# SchedaRobotica.net
KiCad netlist of a schematic drawn in EAGLE
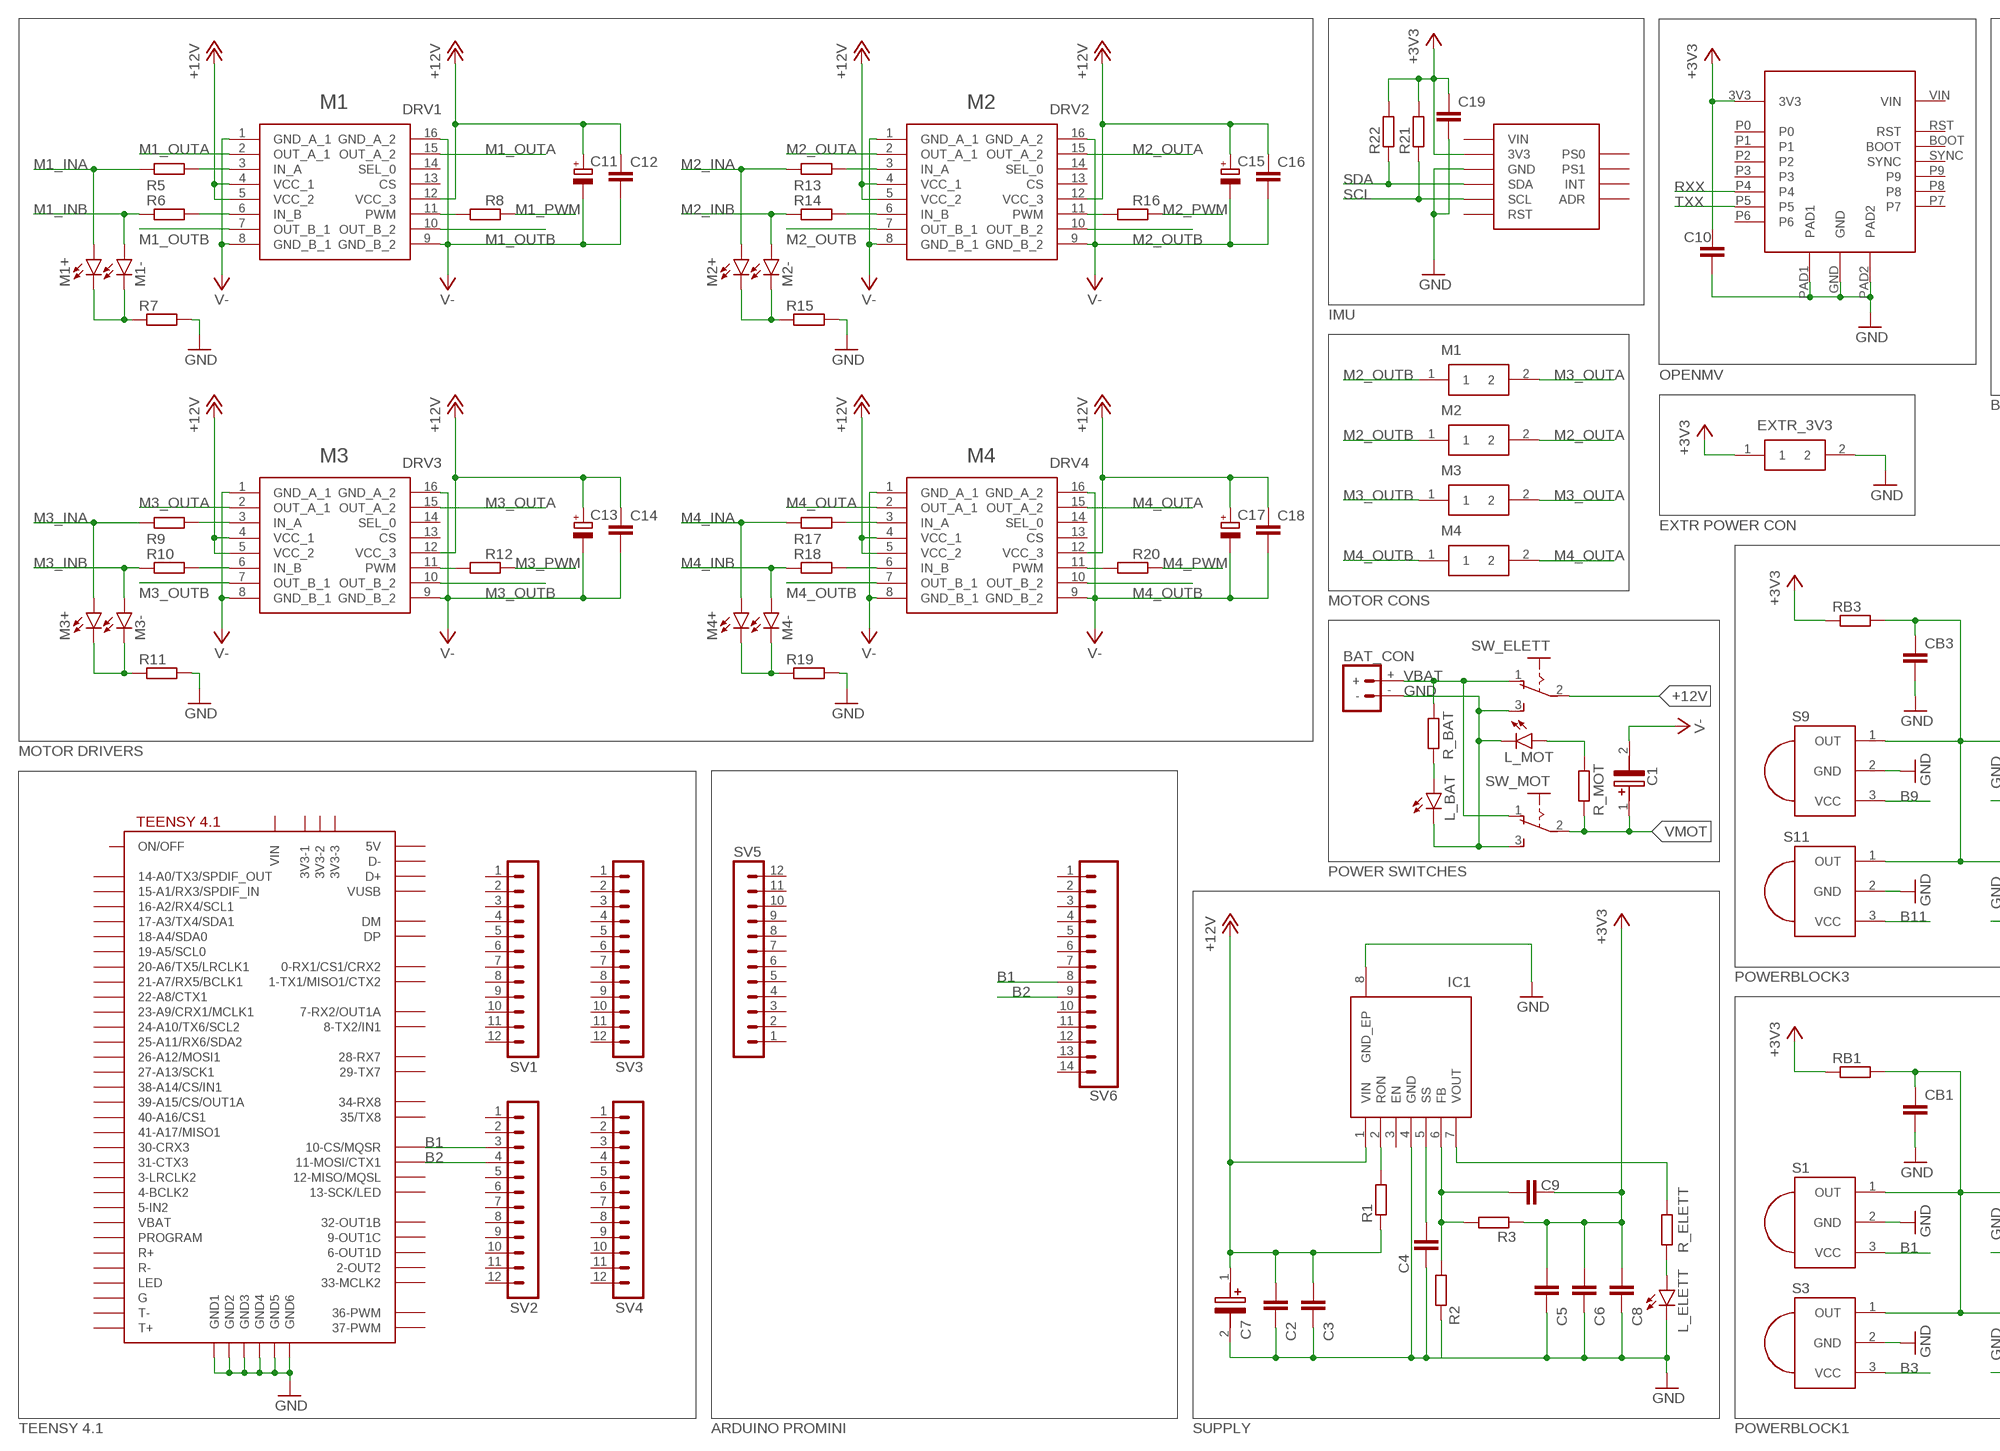
[diagram p0: schematic, sheet 1, part 1 of 2]
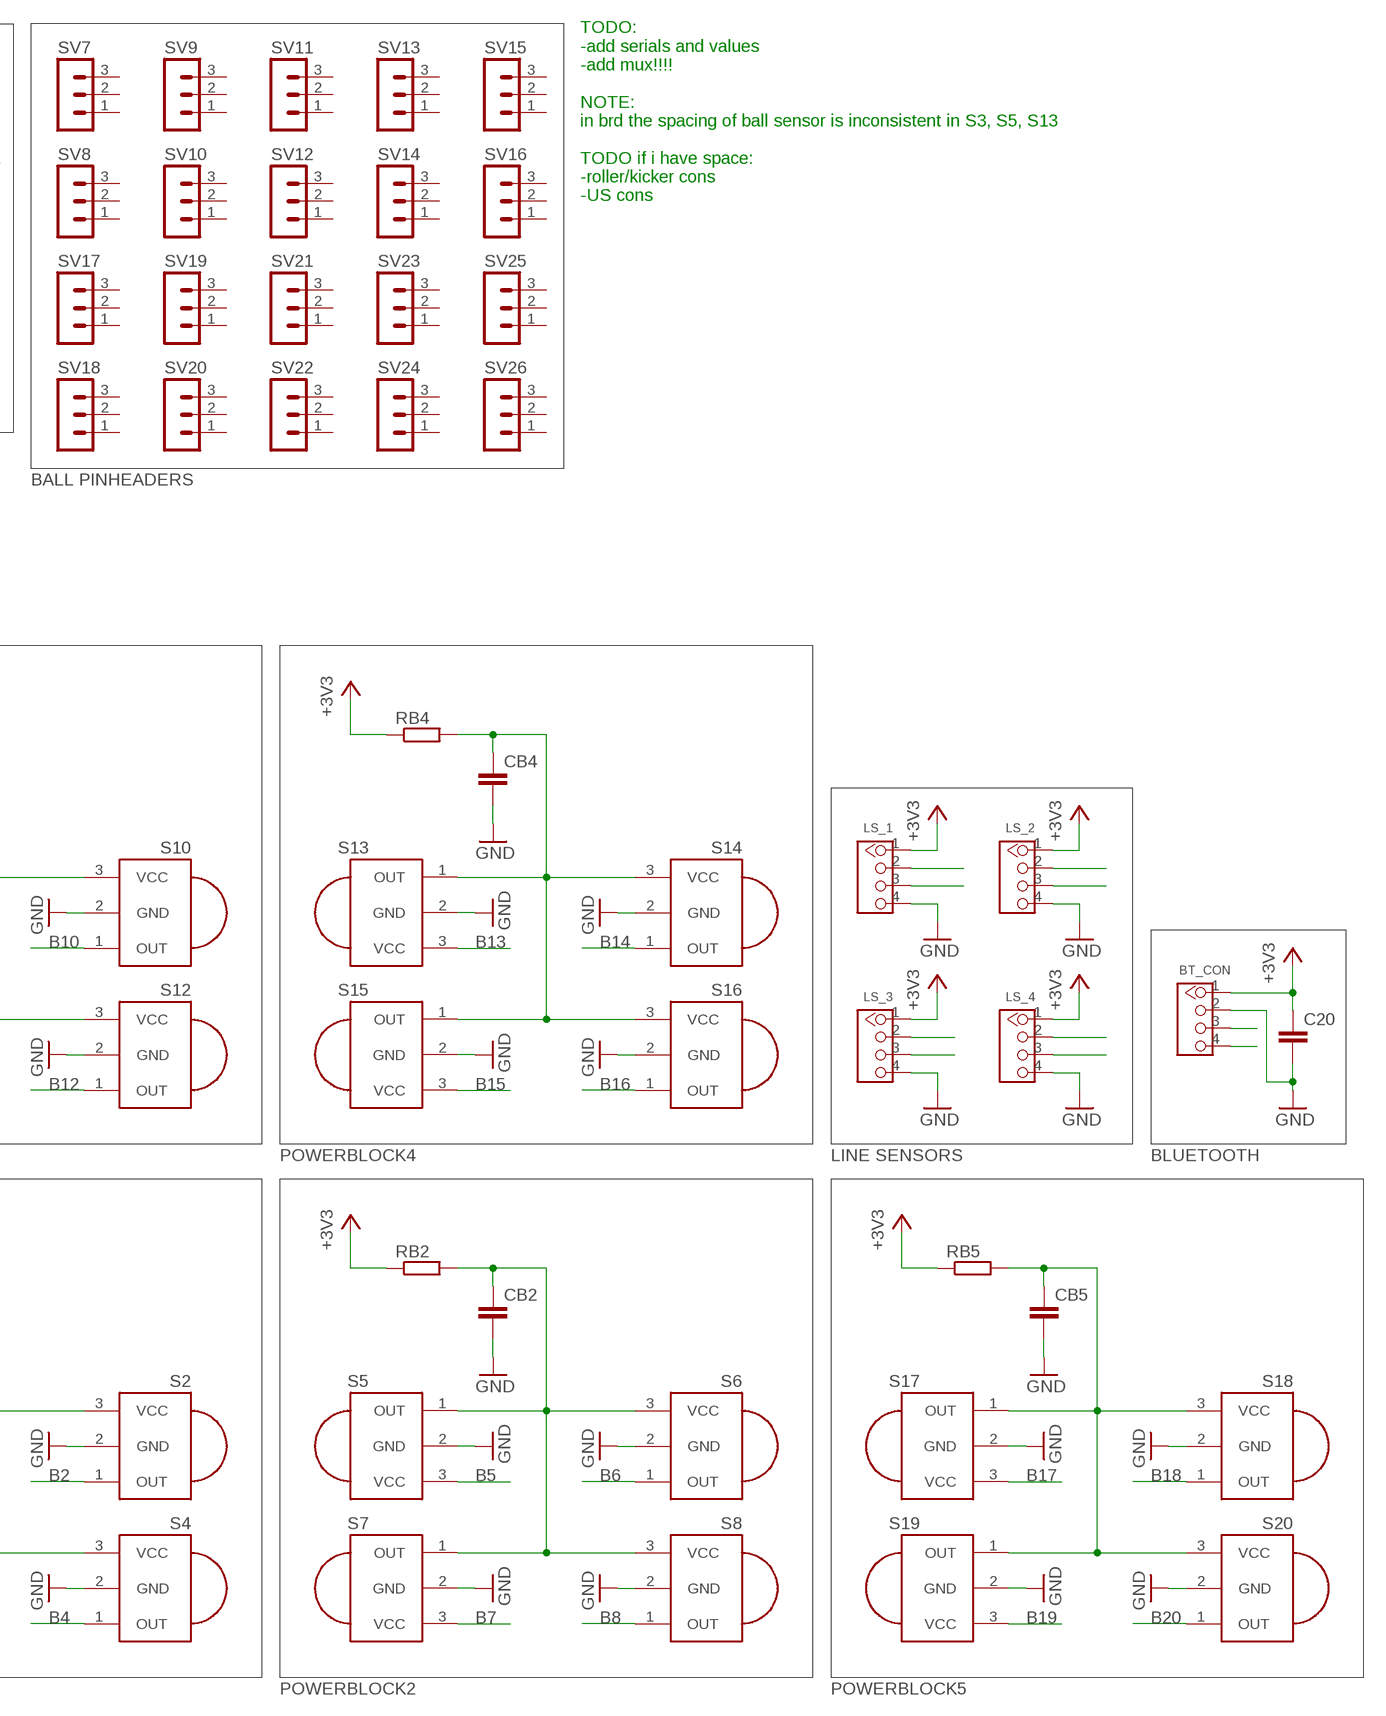
[diagram p1: schematic, sheet 1, part 2 of 2]

(export (version "E")
  (design (tool "Eeschema 10.0.6"))
  (components
    (comp (ref "BAT_CON")
      (value "BATTERY_CONN_DEANS")
      (footprint "eagle-import:DEANS")
      (libsource (lib "eagle-import") (part "BATTERY_CONN_DEANS"))
    )
    (comp (ref "BT_CON")
      (value "4P-2.0")
      (footprint "eagle-import:HW4-2.0")
      (libsource (lib "eagle-import") (part "GROVE-CONNECTOR-DIP(4P-2.0)"))
    )
    (comp (ref "C1")
      (value "EEV-FK1C152Q")
      (footprint "eagle-import:FKV(H13)")
      (fields (field (name "MOUSER_PART_NUMBER") "667-EEV-FK1C152Q"))
      (libsource (lib "eagle-import") (part "EEV-FK1C152Q"))
    )
    (comp (ref "C2")
      (value "100n")
      (footprint "eagle-import:C0805")
      (libsource (lib "eagle-import") (part "C-EUC0805"))
    )
    (comp (ref "C3")
      (value "100n")
      (footprint "eagle-import:C0805")
      (libsource (lib "eagle-import") (part "C-EUC0805"))
    )
    (comp (ref "C4")
      (value "22n")
      (footprint "eagle-import:C0805")
      (libsource (lib "eagle-import") (part "C-EUC0805"))
    )
    (comp (ref "C5")
      (value "100u")
      (footprint "eagle-import:C1206")
      (libsource (lib "eagle-import") (part "C-EUC1206"))
    )
    (comp (ref "C6")
      (value "100u")
      (footprint "eagle-import:C1206")
      (libsource (lib "eagle-import") (part "C-EUC1206"))
    )
    (comp (ref "C7")
      (value "EEV-FK1C152Q")
      (footprint "eagle-import:FKV(H13)")
      (fields (field (name "MOUSER_PART_NUMBER") "667-EEV-FK1C152Q"))
      (libsource (lib "eagle-import") (part "EEV-FK1C152Q"))
    )
    (comp (ref "C8")
      (value "100n")
      (footprint "eagle-import:C0805")
      (libsource (lib "eagle-import") (part "C-EUC0805"))
    )
    (comp (ref "C9")
      (value "22n")
      (footprint "eagle-import:C0805")
      (libsource (lib "eagle-import") (part "C-EUC0805"))
    )
    (comp (ref "C10")
      (value "100u")
      (footprint "eagle-import:C1206")
      (libsource (lib "eagle-import") (part "C-EUC1206"))
    )
    (comp (ref "C11")
      (value "CPOL-EUE")
      (footprint "eagle-import:PANASONIC_E")
      (libsource (lib "eagle-import") (part "CPOL-EUE"))
    )
    (comp (ref "C12")
      (value "C-EUC0805")
      (footprint "eagle-import:C0805")
      (libsource (lib "eagle-import") (part "C-EUC0805"))
    )
    (comp (ref "C13")
      (value "CPOL-EUE")
      (footprint "eagle-import:PANASONIC_E")
      (libsource (lib "eagle-import") (part "CPOL-EUE"))
    )
    (comp (ref "C14")
      (value "C-EUC0805")
      (footprint "eagle-import:C0805")
      (libsource (lib "eagle-import") (part "C-EUC0805"))
    )
    (comp (ref "C15")
      (value "CPOL-EUE")
      (footprint "eagle-import:PANASONIC_E")
      (libsource (lib "eagle-import") (part "CPOL-EUE"))
    )
    (comp (ref "C16")
      (value "C-EUC0805")
      (footprint "eagle-import:C0805")
      (libsource (lib "eagle-import") (part "C-EUC0805"))
    )
    (comp (ref "C17")
      (value "CPOL-EUE")
      (footprint "eagle-import:PANASONIC_E")
      (libsource (lib "eagle-import") (part "CPOL-EUE"))
    )
    (comp (ref "C18")
      (value "C-EUC0805")
      (footprint "eagle-import:C0805")
      (libsource (lib "eagle-import") (part "C-EUC0805"))
    )
    (comp (ref "C19")
      (value "1u")
      (footprint "eagle-import:C0805")
      (libsource (lib "eagle-import") (part "C-EUC0805"))
    )
    (comp (ref "C20")
      (value "1u")
      (footprint "eagle-import:C0805")
      (libsource (lib "eagle-import") (part "C-EUC0805"))
    )
    (comp (ref "CB1")
      (value "C-EUC0805")
      (footprint "eagle-import:C0805")
      (libsource (lib "eagle-import") (part "C-EUC0805"))
    )
    (comp (ref "CB2")
      (value "C-EUC0805")
      (footprint "eagle-import:C0805")
      (libsource (lib "eagle-import") (part "C-EUC0805"))
    )
    (comp (ref "CB3")
      (value "C-EUC0805")
      (footprint "eagle-import:C0805")
      (libsource (lib "eagle-import") (part "C-EUC0805"))
    )
    (comp (ref "CB4")
      (value "C-EUC0805")
      (footprint "eagle-import:C0805")
      (libsource (lib "eagle-import") (part "C-EUC0805"))
    )
    (comp (ref "CB5")
      (value "C-EUC0805")
      (footprint "eagle-import:C0805")
      (libsource (lib "eagle-import") (part "C-EUC0805"))
    )
    (comp (ref "DRV1")
      (value "VNH7070ASTR")
      (footprint "eagle-import:SOIC127P600X175-16N")
      (fields
        (field (name "MOUSER_PART_NUMBER") "511-VNH7070ASTR")
        (field (name "RS_PART_NUMBER") "1647017P")
      )
      (libsource (lib "eagle-import") (part "VNH7070ASTR"))
    )
    (comp (ref "DRV2")
      (value "VNH7070ASTR")
      (footprint "eagle-import:SOIC127P600X175-16N")
      (fields
        (field (name "MOUSER_PART_NUMBER") "511-VNH7070ASTR")
        (field (name "RS_PART_NUMBER") "1647017P")
      )
      (libsource (lib "eagle-import") (part "VNH7070ASTR"))
    )
    (comp (ref "DRV3")
      (value "VNH7070ASTR")
      (footprint "eagle-import:SOIC127P600X175-16N")
      (fields
        (field (name "MOUSER_PART_NUMBER") "511-VNH7070ASTR")
        (field (name "RS_PART_NUMBER") "1647017P")
      )
      (libsource (lib "eagle-import") (part "VNH7070ASTR"))
    )
    (comp (ref "DRV4")
      (value "VNH7070ASTR")
      (footprint "eagle-import:SOIC127P600X175-16N")
      (fields
        (field (name "MOUSER_PART_NUMBER") "511-VNH7070ASTR")
        (field (name "RS_PART_NUMBER") "1647017P")
      )
      (libsource (lib "eagle-import") (part "VNH7070ASTR"))
    )
    (comp (ref "EXTR_3V3")
      (value "43650-0201")
      (footprint "eagle-import:43650-0200")
      (fields (field (name "MOUSER_PART_NUMBER") "538-43650-0201"))
      (libsource (lib "eagle-import") (part "43650-0201"))
    )
    (comp (ref "IC1")
      (value "LMZ14202TZE-ADJ_NOPB")
      (footprint "eagle-import:NDW0007A")
      (fields
        (field (name "MANUFACTURER_PART_NUMBER") "LMZ14202TZE-ADJ/NOPB")
        (field (name "MOUSER_PART_NUMBER") "926-LM14202TZEADJNPB")
        (field (name "RS_PART_NUMBER") "7981195P")
      )
      (libsource (lib "eagle-import") (part "LMZ14202TZE-ADJ_NOPB"))
    )
    (comp (ref "LS_1")
      (value "4P-2.0")
      (footprint "eagle-import:HW4-2.0")
      (libsource (lib "eagle-import") (part "GROVE-CONNECTOR-DIP(4P-2.0)"))
    )
    (comp (ref "LS_2")
      (value "4P-2.0")
      (footprint "eagle-import:HW4-2.0")
      (libsource (lib "eagle-import") (part "GROVE-CONNECTOR-DIP(4P-2.0)"))
    )
    (comp (ref "LS_3")
      (value "4P-2.0")
      (footprint "eagle-import:HW4-2.0")
      (libsource (lib "eagle-import") (part "GROVE-CONNECTOR-DIP(4P-2.0)"))
    )
    (comp (ref "LS_4")
      (value "4P-2.0")
      (footprint "eagle-import:HW4-2.0")
      (libsource (lib "eagle-import") (part "GROVE-CONNECTOR-DIP(4P-2.0)"))
    )
    (comp (ref "L_BAT")
      (value "LEDCHIPLED_1206")
      (footprint "eagle-import:CHIPLED_1206")
      (libsource (lib "eagle-import") (part "LEDCHIPLED_1206"))
    )
    (comp (ref "L_ELETT")
      (value "LEDCHIPLED_1206")
      (footprint "eagle-import:CHIPLED_1206")
      (libsource (lib "eagle-import") (part "LEDCHIPLED_1206"))
    )
    (comp (ref "L_MOT")
      (value "LEDCHIPLED_1206")
      (footprint "eagle-import:CHIPLED_1206")
      (libsource (lib "eagle-import") (part "LEDCHIPLED_1206"))
    )
    (comp (ref "M1")
      (value "43650-0201")
      (footprint "eagle-import:43650-0200")
      (fields (field (name "MOUSER_PART_NUMBER") "538-43650-0201"))
      (libsource (lib "eagle-import") (part "43650-0201"))
    )
    (comp (ref "M1+")
      (value "LEDCHIPLED_1206")
      (footprint "eagle-import:CHIPLED_1206")
      (libsource (lib "eagle-import") (part "LEDCHIPLED_1206"))
    )
    (comp (ref "M1-")
      (value "LEDCHIPLED_1206")
      (footprint "eagle-import:CHIPLED_1206")
      (libsource (lib "eagle-import") (part "LEDCHIPLED_1206"))
    )
    (comp (ref "M2")
      (value "43650-0201")
      (footprint "eagle-import:43650-0200")
      (fields (field (name "MOUSER_PART_NUMBER") "538-43650-0201"))
      (libsource (lib "eagle-import") (part "43650-0201"))
    )
    (comp (ref "M2+")
      (value "LEDCHIPLED_1206")
      (footprint "eagle-import:CHIPLED_1206")
      (libsource (lib "eagle-import") (part "LEDCHIPLED_1206"))
    )
    (comp (ref "M2-")
      (value "LEDCHIPLED_1206")
      (footprint "eagle-import:CHIPLED_1206")
      (libsource (lib "eagle-import") (part "LEDCHIPLED_1206"))
    )
    (comp (ref "M3")
      (value "43650-0201")
      (footprint "eagle-import:43650-0200")
      (fields (field (name "MOUSER_PART_NUMBER") "538-43650-0201"))
      (libsource (lib "eagle-import") (part "43650-0201"))
    )
    (comp (ref "M3+")
      (value "LEDCHIPLED_1206")
      (footprint "eagle-import:CHIPLED_1206")
      (libsource (lib "eagle-import") (part "LEDCHIPLED_1206"))
    )
    (comp (ref "M3-")
      (value "LEDCHIPLED_1206")
      (footprint "eagle-import:CHIPLED_1206")
      (libsource (lib "eagle-import") (part "LEDCHIPLED_1206"))
    )
    (comp (ref "M4")
      (value "43650-0201")
      (footprint "eagle-import:43650-0200")
      (fields (field (name "MOUSER_PART_NUMBER") "538-43650-0201"))
      (libsource (lib "eagle-import") (part "43650-0201"))
    )
    (comp (ref "M4+")
      (value "LEDCHIPLED_1206")
      (footprint "eagle-import:CHIPLED_1206")
      (libsource (lib "eagle-import") (part "LEDCHIPLED_1206"))
    )
    (comp (ref "M4-")
      (value "LEDCHIPLED_1206")
      (footprint "eagle-import:CHIPLED_1206")
      (libsource (lib "eagle-import") (part "LEDCHIPLED_1206"))
    )
    (comp (ref "R1")
      (value "61,9k")
      (footprint "eagle-import:M0805")
      (libsource (lib "eagle-import") (part "R-EU_M0805"))
    )
    (comp (ref "R2")
      (value "1,07k")
      (footprint "eagle-import:M0805")
      (libsource (lib "eagle-import") (part "R-EU_M0805"))
    )
    (comp (ref "R3")
      (value "3,32k")
      (footprint "eagle-import:M0805")
      (libsource (lib "eagle-import") (part "R-EU_M0805"))
    )
    (comp (ref "R5")
      (value "R-EU_M0805")
      (footprint "eagle-import:M0805")
      (libsource (lib "eagle-import") (part "R-EU_M0805"))
    )
    (comp (ref "R6")
      (value "R-EU_M0805")
      (footprint "eagle-import:M0805")
      (libsource (lib "eagle-import") (part "R-EU_M0805"))
    )
    (comp (ref "R7")
      (value "R-EU_M0805")
      (footprint "eagle-import:M0805")
      (libsource (lib "eagle-import") (part "R-EU_M0805"))
    )
    (comp (ref "R8")
      (value "R-EU_M0805")
      (footprint "eagle-import:M0805")
      (libsource (lib "eagle-import") (part "R-EU_M0805"))
    )
    (comp (ref "R9")
      (value "R-EU_M0805")
      (footprint "eagle-import:M0805")
      (libsource (lib "eagle-import") (part "R-EU_M0805"))
    )
    (comp (ref "R10")
      (value "R-EU_M0805")
      (footprint "eagle-import:M0805")
      (libsource (lib "eagle-import") (part "R-EU_M0805"))
    )
    (comp (ref "R11")
      (value "R-EU_M0805")
      (footprint "eagle-import:M0805")
      (libsource (lib "eagle-import") (part "R-EU_M0805"))
    )
    (comp (ref "R12")
      (value "R-EU_M0805")
      (footprint "eagle-import:M0805")
      (libsource (lib "eagle-import") (part "R-EU_M0805"))
    )
    (comp (ref "R13")
      (value "R-EU_M0805")
      (footprint "eagle-import:M0805")
      (libsource (lib "eagle-import") (part "R-EU_M0805"))
    )
    (comp (ref "R14")
      (value "R-EU_M0805")
      (footprint "eagle-import:M0805")
      (libsource (lib "eagle-import") (part "R-EU_M0805"))
    )
    (comp (ref "R15")
      (value "R-EU_M0805")
      (footprint "eagle-import:M0805")
      (libsource (lib "eagle-import") (part "R-EU_M0805"))
    )
    (comp (ref "R16")
      (value "R-EU_M0805")
      (footprint "eagle-import:M0805")
      (libsource (lib "eagle-import") (part "R-EU_M0805"))
    )
    (comp (ref "R17")
      (value "R-EU_M0805")
      (footprint "eagle-import:M0805")
      (libsource (lib "eagle-import") (part "R-EU_M0805"))
    )
    (comp (ref "R18")
      (value "R-EU_M0805")
      (footprint "eagle-import:M0805")
      (libsource (lib "eagle-import") (part "R-EU_M0805"))
    )
    (comp (ref "R19")
      (value "R-EU_M0805")
      (footprint "eagle-import:M0805")
      (libsource (lib "eagle-import") (part "R-EU_M0805"))
    )
    (comp (ref "R20")
      (value "R-EU_M0805")
      (footprint "eagle-import:M0805")
      (libsource (lib "eagle-import") (part "R-EU_M0805"))
    )
    (comp (ref "R21")
      (value "10k")
      (footprint "eagle-import:M0805")
      (libsource (lib "eagle-import") (part "R-EU_M0805"))
    )
    (comp (ref "R22")
      (value "10k")
      (footprint "eagle-import:M0805")
      (libsource (lib "eagle-import") (part "R-EU_M0805"))
    )
    (comp (ref "RB1")
      (value "R-EU_M0805")
      (footprint "eagle-import:M0805")
      (libsource (lib "eagle-import") (part "R-EU_M0805"))
    )
    (comp (ref "RB2")
      (value "R-EU_M0805")
      (footprint "eagle-import:M0805")
      (libsource (lib "eagle-import") (part "R-EU_M0805"))
    )
    (comp (ref "RB3")
      (value "R-EU_M0805")
      (footprint "eagle-import:M0805")
      (libsource (lib "eagle-import") (part "R-EU_M0805"))
    )
    (comp (ref "RB4")
      (value "R-EU_M0805")
      (footprint "eagle-import:M0805")
      (libsource (lib "eagle-import") (part "R-EU_M0805"))
    )
    (comp (ref "RB5")
      (value "R-EU_M0805")
      (footprint "eagle-import:M0805")
      (libsource (lib "eagle-import") (part "R-EU_M0805"))
    )
    (comp (ref "R_BAT")
      (value "R-EU_M0805")
      (footprint "eagle-import:M0805")
      (libsource (lib "eagle-import") (part "R-EU_M0805"))
    )
    (comp (ref "R_ELETT")
      (value "R-EU_M0805")
      (footprint "eagle-import:M0805")
      (libsource (lib "eagle-import") (part "R-EU_M0805"))
    )
    (comp (ref "R_MOT")
      (value "R-EU_M0805")
      (footprint "eagle-import:M0805")
      (libsource (lib "eagle-import") (part "R-EU_M0805"))
    )
    (comp (ref "S1")
      (value "PNA460XM")
      (footprint "eagle-import:PNA460XM")
      (libsource (lib "eagle-import") (part "PNA460XM"))
    )
    (comp (ref "S2")
      (value "PNA460XM")
      (footprint "eagle-import:PNA460XM")
      (libsource (lib "eagle-import") (part "PNA460XM"))
    )
    (comp (ref "S3")
      (value "PNA460XM")
      (footprint "eagle-import:PNA460XM")
      (libsource (lib "eagle-import") (part "PNA460XM"))
    )
    (comp (ref "S4")
      (value "PNA460XM")
      (footprint "eagle-import:PNA460XM")
      (libsource (lib "eagle-import") (part "PNA460XM"))
    )
    (comp (ref "S5")
      (value "PNA460XM")
      (footprint "eagle-import:PNA460XM")
      (libsource (lib "eagle-import") (part "PNA460XM"))
    )
    (comp (ref "S6")
      (value "PNA460XM")
      (footprint "eagle-import:PNA460XM")
      (libsource (lib "eagle-import") (part "PNA460XM"))
    )
    (comp (ref "S7")
      (value "PNA460XM")
      (footprint "eagle-import:PNA460XM")
      (libsource (lib "eagle-import") (part "PNA460XM"))
    )
    (comp (ref "S8")
      (value "PNA460XM")
      (footprint "eagle-import:PNA460XM")
      (libsource (lib "eagle-import") (part "PNA460XM"))
    )
    (comp (ref "S9")
      (value "PNA460XM")
      (footprint "eagle-import:PNA460XM")
      (libsource (lib "eagle-import") (part "PNA460XM"))
    )
    (comp (ref "S10")
      (value "PNA460XM")
      (footprint "eagle-import:PNA460XM")
      (libsource (lib "eagle-import") (part "PNA460XM"))
    )
    (comp (ref "S11")
      (value "PNA460XM")
      (footprint "eagle-import:PNA460XM")
      (libsource (lib "eagle-import") (part "PNA460XM"))
    )
    (comp (ref "S12")
      (value "PNA460XM")
      (footprint "eagle-import:PNA460XM")
      (libsource (lib "eagle-import") (part "PNA460XM"))
    )
    (comp (ref "S13")
      (value "PNA460XM")
      (footprint "eagle-import:PNA460XM")
      (libsource (lib "eagle-import") (part "PNA460XM"))
    )
    (comp (ref "S14")
      (value "PNA460XM")
      (footprint "eagle-import:PNA460XM")
      (libsource (lib "eagle-import") (part "PNA460XM"))
    )
    (comp (ref "S15")
      (value "PNA460XM")
      (footprint "eagle-import:PNA460XM")
      (libsource (lib "eagle-import") (part "PNA460XM"))
    )
    (comp (ref "S16")
      (value "PNA460XM")
      (footprint "eagle-import:PNA460XM")
      (libsource (lib "eagle-import") (part "PNA460XM"))
    )
    (comp (ref "S17")
      (value "PNA460XM")
      (footprint "eagle-import:PNA460XM")
      (libsource (lib "eagle-import") (part "PNA460XM"))
    )
    (comp (ref "S18")
      (value "PNA460XM")
      (footprint "eagle-import:PNA460XM")
      (libsource (lib "eagle-import") (part "PNA460XM"))
    )
    (comp (ref "S19")
      (value "PNA460XM")
      (footprint "eagle-import:PNA460XM")
      (libsource (lib "eagle-import") (part "PNA460XM"))
    )
    (comp (ref "S20")
      (value "PNA460XM")
      (footprint "eagle-import:PNA460XM")
      (libsource (lib "eagle-import") (part "PNA460XM"))
    )
    (comp (ref "SV1")
      (value "MA12-1")
      (footprint "eagle-import:MA12-1")
      (libsource (lib "eagle-import") (part "MA12-1"))
    )
    (comp (ref "SV2")
      (value "MA12-1")
      (footprint "eagle-import:MA12-1")
      (libsource (lib "eagle-import") (part "MA12-1"))
    )
    (comp (ref "SV3")
      (value "MA12-1")
      (footprint "eagle-import:MA12-1")
      (libsource (lib "eagle-import") (part "MA12-1"))
    )
    (comp (ref "SV4")
      (value "MA12-1")
      (footprint "eagle-import:MA12-1")
      (libsource (lib "eagle-import") (part "MA12-1"))
    )
    (comp (ref "SV5")
      (value "MA12-1")
      (footprint "eagle-import:MA12-1")
      (libsource (lib "eagle-import") (part "MA12-1"))
    )
    (comp (ref "SV6")
      (value "CONN_14LONGPADS")
      (footprint "eagle-import:1X14-LONGPADS")
      (libsource (lib "eagle-import") (part "CONN_14LONGPADS"))
    )
    (comp (ref "SV7")
      (value "MA03-1")
      (footprint "eagle-import:MA03-1")
      (libsource (lib "eagle-import") (part "MA03-1"))
    )
    (comp (ref "SV8")
      (value "MA03-1")
      (footprint "eagle-import:MA03-1")
      (libsource (lib "eagle-import") (part "MA03-1"))
    )
    (comp (ref "SV9")
      (value "MA03-1")
      (footprint "eagle-import:MA03-1")
      (libsource (lib "eagle-import") (part "MA03-1"))
    )
    (comp (ref "SV10")
      (value "MA03-1")
      (footprint "eagle-import:MA03-1")
      (libsource (lib "eagle-import") (part "MA03-1"))
    )
    (comp (ref "SV11")
      (value "MA03-1")
      (footprint "eagle-import:MA03-1")
      (libsource (lib "eagle-import") (part "MA03-1"))
    )
    (comp (ref "SV12")
      (value "MA03-1")
      (footprint "eagle-import:MA03-1")
      (libsource (lib "eagle-import") (part "MA03-1"))
    )
    (comp (ref "SV13")
      (value "MA03-1")
      (footprint "eagle-import:MA03-1")
      (libsource (lib "eagle-import") (part "MA03-1"))
    )
    (comp (ref "SV14")
      (value "MA03-1")
      (footprint "eagle-import:MA03-1")
      (libsource (lib "eagle-import") (part "MA03-1"))
    )
    (comp (ref "SV15")
      (value "MA03-1")
      (footprint "eagle-import:MA03-1")
      (libsource (lib "eagle-import") (part "MA03-1"))
    )
    (comp (ref "SV16")
      (value "MA03-1")
      (footprint "eagle-import:MA03-1")
      (libsource (lib "eagle-import") (part "MA03-1"))
    )
    (comp (ref "SV17")
      (value "MA03-1")
      (footprint "eagle-import:MA03-1")
      (libsource (lib "eagle-import") (part "MA03-1"))
    )
    (comp (ref "SV18")
      (value "MA03-1")
      (footprint "eagle-import:MA03-1")
      (libsource (lib "eagle-import") (part "MA03-1"))
    )
    (comp (ref "SV19")
      (value "MA03-1")
      (footprint "eagle-import:MA03-1")
      (libsource (lib "eagle-import") (part "MA03-1"))
    )
    (comp (ref "SV20")
      (value "MA03-1")
      (footprint "eagle-import:MA03-1")
      (libsource (lib "eagle-import") (part "MA03-1"))
    )
    (comp (ref "SV21")
      (value "MA03-1")
      (footprint "eagle-import:MA03-1")
      (libsource (lib "eagle-import") (part "MA03-1"))
    )
    (comp (ref "SV22")
      (value "MA03-1")
      (footprint "eagle-import:MA03-1")
      (libsource (lib "eagle-import") (part "MA03-1"))
    )
    (comp (ref "SV23")
      (value "MA03-1")
      (footprint "eagle-import:MA03-1")
      (libsource (lib "eagle-import") (part "MA03-1"))
    )
    (comp (ref "SV24")
      (value "MA03-1")
      (footprint "eagle-import:MA03-1")
      (libsource (lib "eagle-import") (part "MA03-1"))
    )
    (comp (ref "SV25")
      (value "MA03-1")
      (footprint "eagle-import:MA03-1")
      (libsource (lib "eagle-import") (part "MA03-1"))
    )
    (comp (ref "SV26")
      (value "MA03-1")
      (footprint "eagle-import:MA03-1")
      (libsource (lib "eagle-import") (part "MA03-1"))
    )
    (comp (ref "SW_ELETT")
      (value "255SB")
      (footprint "eagle-import:255SB")
      (libsource (lib "eagle-import") (part "255SB"))
    )
    (comp (ref "SW_MOT")
      (value "255SB")
      (footprint "eagle-import:255SB")
      (libsource (lib "eagle-import") (part "255SB"))
    )
    (comp (ref "U$1")
      (value "TEENSY41")
      (footprint "eagle-import:TEENSY41")
      (libsource (lib "eagle-import") (part "TEENSY41"))
    )
    (comp (ref "U$2")
      (value "OPENMV_H7")
      (footprint "eagle-import:OPENMV_H7")
      (libsource (lib "eagle-import") (part "OPENMV_H7"))
    )
    (comp (ref "U$3")
      (value "BNO055_BNO055")
      (footprint "eagle-import:BNO055_BNO055")
      (libsource (lib "eagle-import") (part "BNO055_BNO055"))
    )
  )
  (nets
    (net (code "1") (name "+3V3") (class "Default")
      (node (ref "BT_CON") (pin "1") (pinfunction "1_1") (pintype "bidirectional"))
      (node (ref "C10") (pin "1") (pinfunction "1_1") (pintype "passive"))
      (node (ref "C19") (pin "1") (pinfunction "1_1") (pintype "passive"))
      (node (ref "C20") (pin "1") (pinfunction "1_1") (pintype "passive"))
      (node (ref "C5") (pin "1") (pinfunction "1_1") (pintype "passive"))
      (node (ref "C6") (pin "1") (pinfunction "1_1") (pintype "passive"))
      (node (ref "C8") (pin "1") (pinfunction "1_1") (pintype "passive"))
      (node (ref "C9") (pin "2") (pinfunction "2_2") (pintype "passive"))
      (node (ref "EXTR_3V3") (pin "1") (pinfunction "1_1") (pintype "bidirectional"))
      (node (ref "LS_1") (pin "1") (pinfunction "1_1") (pintype "bidirectional"))
      (node (ref "LS_2") (pin "1") (pinfunction "1_1") (pintype "bidirectional"))
      (node (ref "LS_3") (pin "1") (pinfunction "1_1") (pintype "bidirectional"))
      (node (ref "LS_4") (pin "1") (pinfunction "1_1") (pintype "bidirectional"))
      (node (ref "R21") (pin "2") (pinfunction "2_2") (pintype "passive"))
      (node (ref "R22") (pin "2") (pinfunction "2_2") (pintype "passive"))
      (node (ref "R3") (pin "1") (pinfunction "1_1") (pintype "passive"))
      (node (ref "RB1") (pin "1") (pinfunction "1_1") (pintype "passive"))
      (node (ref "RB2") (pin "1") (pinfunction "1_1") (pintype "passive"))
      (node (ref "RB3") (pin "1") (pinfunction "1_1") (pintype "passive"))
      (node (ref "RB4") (pin "1") (pinfunction "1_1") (pintype "passive"))
      (node (ref "RB5") (pin "1") (pinfunction "1_1") (pintype "passive"))
      (node (ref "U$2") (pin "3V3") (pinfunction "3V3_3V3") (pintype "bidirectional"))
      (node (ref "U$3") (pin "3V3") (pinfunction "3V3_3V3") (pintype "bidirectional"))
    )
    (net (code "2") (name "+12V") (class "Default")
      (node (ref "C11") (pin "+") (pinfunction "+_+") (pintype "passive"))
      (node (ref "C12") (pin "1") (pinfunction "1_1") (pintype "passive"))
      (node (ref "C13") (pin "+") (pinfunction "+_+") (pintype "passive"))
      (node (ref "C14") (pin "1") (pinfunction "1_1") (pintype "passive"))
      (node (ref "C15") (pin "+") (pinfunction "+_+") (pintype "passive"))
      (node (ref "C16") (pin "1") (pinfunction "1_1") (pintype "passive"))
      (node (ref "C17") (pin "+") (pinfunction "+_+") (pintype "passive"))
      (node (ref "C18") (pin "1") (pinfunction "1_1") (pintype "passive"))
      (node (ref "C2") (pin "1") (pinfunction "1_1") (pintype "passive"))
      (node (ref "C3") (pin "1") (pinfunction "1_1") (pintype "passive"))
      (node (ref "C7") (pin "1") (pinfunction "+_1") (pintype "bidirectional"))
      (node (ref "DRV1") (pin "12") (pinfunction "VCC_3_12") (pintype "bidirectional"))
      (node (ref "DRV1") (pin "4") (pinfunction "VCC_1_4") (pintype "bidirectional"))
      (node (ref "DRV1") (pin "5") (pinfunction "VCC_2_5") (pintype "bidirectional"))
      (node (ref "DRV2") (pin "12") (pinfunction "VCC_3_12") (pintype "bidirectional"))
      (node (ref "DRV2") (pin "4") (pinfunction "VCC_1_4") (pintype "bidirectional"))
      (node (ref "DRV2") (pin "5") (pinfunction "VCC_2_5") (pintype "bidirectional"))
      (node (ref "DRV3") (pin "12") (pinfunction "VCC_3_12") (pintype "bidirectional"))
      (node (ref "DRV3") (pin "4") (pinfunction "VCC_1_4") (pintype "bidirectional"))
      (node (ref "DRV3") (pin "5") (pinfunction "VCC_2_5") (pintype "bidirectional"))
      (node (ref "DRV4") (pin "12") (pinfunction "VCC_3_12") (pintype "bidirectional"))
      (node (ref "DRV4") (pin "4") (pinfunction "VCC_1_4") (pintype "bidirectional"))
      (node (ref "DRV4") (pin "5") (pinfunction "VCC_2_5") (pintype "bidirectional"))
      (node (ref "IC1") (pin "1") (pinfunction "VIN_1") (pintype "input"))
      (node (ref "R1") (pin "1") (pinfunction "1_1") (pintype "passive"))
      (node (ref "SW_ELETT") (pin "2") (pinfunction "P_2") (pintype "passive"))
    )
    (net (code "3") (name "/B1") (class "Default")
      (node (ref "S1") (pin "3") (pinfunction "VCC_3") (pintype "power_in"))
      (node (ref "SV2") (pin "3") (pinfunction "3_3") (pintype "passive"))
      (node (ref "SV6") (pin "8") (pinfunction "8_8") (pintype "passive"))
      (node (ref "U$1") (pin "10-CS\\MQSR") (pinfunction "10-CS/MQSR_10-CS\\MQSR") (pintype "bidirectional"))
    )
    (net (code "4") (name "/B2") (class "Default")
      (node (ref "S2") (pin "1") (pinfunction "OUT_1") (pintype "output"))
      (node (ref "SV2") (pin "4") (pinfunction "4_4") (pintype "passive"))
      (node (ref "SV6") (pin "9") (pinfunction "9_9") (pintype "passive"))
      (node (ref "U$1") (pin "11-MOSI/CTX1") (pinfunction "11-MOSI/CTX1_11-MOSI/CTX1") (pintype "bidirectional"))
    )
    (net (code "5") (name "/B3") (class "Default")
      (node (ref "S3") (pin "3") (pinfunction "VCC_3") (pintype "power_in"))
    )
    (net (code "6") (name "/B4") (class "Default")
      (node (ref "S4") (pin "1") (pinfunction "OUT_1") (pintype "output"))
    )
    (net (code "7") (name "/B5") (class "Default")
      (node (ref "S5") (pin "3") (pinfunction "VCC_3") (pintype "power_in"))
    )
    (net (code "8") (name "/B6") (class "Default")
      (node (ref "S6") (pin "1") (pinfunction "OUT_1") (pintype "output"))
    )
    (net (code "9") (name "/B7") (class "Default")
      (node (ref "S7") (pin "3") (pinfunction "VCC_3") (pintype "power_in"))
    )
    (net (code "10") (name "/B8") (class "Default")
      (node (ref "S8") (pin "1") (pinfunction "OUT_1") (pintype "output"))
    )
    (net (code "11") (name "/B9") (class "Default")
      (node (ref "S9") (pin "3") (pinfunction "VCC_3") (pintype "power_in"))
    )
    (net (code "12") (name "/B10") (class "Default")
      (node (ref "S10") (pin "1") (pinfunction "OUT_1") (pintype "output"))
    )
    (net (code "13") (name "/B11") (class "Default")
      (node (ref "S11") (pin "3") (pinfunction "VCC_3") (pintype "power_in"))
    )
    (net (code "14") (name "/B12") (class "Default")
      (node (ref "S12") (pin "1") (pinfunction "OUT_1") (pintype "output"))
    )
    (net (code "15") (name "/B13") (class "Default")
      (node (ref "S13") (pin "3") (pinfunction "VCC_3") (pintype "power_in"))
    )
    (net (code "16") (name "/B14") (class "Default")
      (node (ref "S14") (pin "1") (pinfunction "OUT_1") (pintype "output"))
    )
    (net (code "17") (name "/B15") (class "Default")
      (node (ref "S15") (pin "3") (pinfunction "VCC_3") (pintype "power_in"))
    )
    (net (code "18") (name "/B16") (class "Default")
      (node (ref "S16") (pin "1") (pinfunction "OUT_1") (pintype "output"))
    )
    (net (code "19") (name "/B17") (class "Default")
      (node (ref "S17") (pin "3") (pinfunction "VCC_3") (pintype "power_in"))
    )
    (net (code "20") (name "/B18") (class "Default")
      (node (ref "S18") (pin "1") (pinfunction "OUT_1") (pintype "output"))
    )
    (net (code "21") (name "/B19") (class "Default")
      (node (ref "S19") (pin "3") (pinfunction "VCC_3") (pintype "power_in"))
    )
    (net (code "22") (name "/B20") (class "Default")
      (node (ref "S20") (pin "1") (pinfunction "OUT_1") (pintype "output"))
    )
    (net (code "23") (name "/M1_INA") (class "Default")
      (node (ref "M1+") (pin "A") (pinfunction "A_A") (pintype "passive"))
      (node (ref "R5") (pin "1") (pinfunction "1_1") (pintype "passive"))
    )
    (net (code "24") (name "/M1_INB") (class "Default")
      (node (ref "M1-") (pin "A") (pinfunction "A_A") (pintype "passive"))
      (node (ref "R6") (pin "1") (pinfunction "1_1") (pintype "passive"))
    )
    (net (code "25") (name "/M1_OUTA") (class "Default")
      (node (ref "DRV1") (pin "15") (pinfunction "OUT_A_2_15") (pintype "bidirectional"))
      (node (ref "DRV1") (pin "2") (pinfunction "OUT_A_1_2") (pintype "bidirectional"))
    )
    (net (code "26") (name "/M1_OUTB") (class "Default")
      (node (ref "DRV1") (pin "10") (pinfunction "OUT_B_2_10") (pintype "bidirectional"))
      (node (ref "DRV1") (pin "7") (pinfunction "OUT_B_1_7") (pintype "bidirectional"))
    )
    (net (code "27") (name "/M1_PWM") (class "Default")
      (node (ref "R8") (pin "2") (pinfunction "2_2") (pintype "passive"))
    )
    (net (code "28") (name "/M2_INA") (class "Default")
      (node (ref "M2+") (pin "A") (pinfunction "A_A") (pintype "passive"))
      (node (ref "R13") (pin "1") (pinfunction "1_1") (pintype "passive"))
    )
    (net (code "29") (name "/M2_INB") (class "Default")
      (node (ref "M2-") (pin "A") (pinfunction "A_A") (pintype "passive"))
      (node (ref "R14") (pin "1") (pinfunction "1_1") (pintype "passive"))
    )
    (net (code "30") (name "/M2_OUTA") (class "Default")
      (node (ref "DRV2") (pin "15") (pinfunction "OUT_A_2_15") (pintype "bidirectional"))
      (node (ref "DRV2") (pin "2") (pinfunction "OUT_A_1_2") (pintype "bidirectional"))
      (node (ref "M2") (pin "2") (pinfunction "2_2") (pintype "bidirectional"))
    )
    (net (code "31") (name "/M2_OUTB") (class "Default")
      (node (ref "DRV2") (pin "10") (pinfunction "OUT_B_2_10") (pintype "bidirectional"))
      (node (ref "DRV2") (pin "7") (pinfunction "OUT_B_1_7") (pintype "bidirectional"))
      (node (ref "M1") (pin "1") (pinfunction "1_1") (pintype "bidirectional"))
      (node (ref "M2") (pin "1") (pinfunction "1_1") (pintype "bidirectional"))
    )
    (net (code "32") (name "/M2_PWM") (class "Default")
      (node (ref "R16") (pin "2") (pinfunction "2_2") (pintype "passive"))
    )
    (net (code "33") (name "/M3_INA") (class "Default")
      (node (ref "M3+") (pin "A") (pinfunction "A_A") (pintype "passive"))
      (node (ref "R9") (pin "1") (pinfunction "1_1") (pintype "passive"))
    )
    (net (code "34") (name "/M3_INB") (class "Default")
      (node (ref "M3-") (pin "A") (pinfunction "A_A") (pintype "passive"))
      (node (ref "R10") (pin "1") (pinfunction "1_1") (pintype "passive"))
    )
    (net (code "35") (name "/M3_OUTA") (class "Default")
      (node (ref "DRV3") (pin "15") (pinfunction "OUT_A_2_15") (pintype "bidirectional"))
      (node (ref "DRV3") (pin "2") (pinfunction "OUT_A_1_2") (pintype "bidirectional"))
      (node (ref "M1") (pin "2") (pinfunction "2_2") (pintype "bidirectional"))
      (node (ref "M3") (pin "2") (pinfunction "2_2") (pintype "bidirectional"))
    )
    (net (code "36") (name "/M3_OUTB") (class "Default")
      (node (ref "DRV3") (pin "10") (pinfunction "OUT_B_2_10") (pintype "bidirectional"))
      (node (ref "DRV3") (pin "7") (pinfunction "OUT_B_1_7") (pintype "bidirectional"))
      (node (ref "M3") (pin "1") (pinfunction "1_1") (pintype "bidirectional"))
    )
    (net (code "37") (name "/M3_PWM") (class "Default")
      (node (ref "R12") (pin "2") (pinfunction "2_2") (pintype "passive"))
    )
    (net (code "38") (name "/M4_INA") (class "Default")
      (node (ref "M4+") (pin "A") (pinfunction "A_A") (pintype "passive"))
      (node (ref "R17") (pin "1") (pinfunction "1_1") (pintype "passive"))
    )
    (net (code "39") (name "/M4_INB") (class "Default")
      (node (ref "M4-") (pin "A") (pinfunction "A_A") (pintype "passive"))
      (node (ref "R18") (pin "1") (pinfunction "1_1") (pintype "passive"))
    )
    (net (code "40") (name "/M4_OUTA") (class "Default")
      (node (ref "DRV4") (pin "15") (pinfunction "OUT_A_2_15") (pintype "bidirectional"))
      (node (ref "DRV4") (pin "2") (pinfunction "OUT_A_1_2") (pintype "bidirectional"))
      (node (ref "M4") (pin "2") (pinfunction "2_2") (pintype "bidirectional"))
    )
    (net (code "41") (name "/M4_OUTB") (class "Default")
      (node (ref "DRV4") (pin "10") (pinfunction "OUT_B_2_10") (pintype "bidirectional"))
      (node (ref "DRV4") (pin "7") (pinfunction "OUT_B_1_7") (pintype "bidirectional"))
      (node (ref "M4") (pin "1") (pinfunction "1_1") (pintype "bidirectional"))
    )
    (net (code "42") (name "/M4_PWM") (class "Default")
      (node (ref "R20") (pin "2") (pinfunction "2_2") (pintype "passive"))
    )
    (net (code "43") (name "/RXX") (class "Default")
      (node (ref "U$2") (pin "P4") (pinfunction "P4_P4") (pintype "bidirectional"))
    )
    (net (code "44") (name "/SCL") (class "Default")
      (node (ref "R21") (pin "1") (pinfunction "1_1") (pintype "passive"))
      (node (ref "U$3") (pin "SCL") (pinfunction "SCL_SCL") (pintype "bidirectional"))
    )
    (net (code "45") (name "/SDA") (class "Default")
      (node (ref "R22") (pin "1") (pinfunction "1_1") (pintype "passive"))
      (node (ref "U$3") (pin "SDA") (pinfunction "SDA_SDA") (pintype "bidirectional"))
    )
    (net (code "46") (name "/TXX") (class "Default")
      (node (ref "U$2") (pin "P5") (pinfunction "P5_P5") (pintype "bidirectional"))
    )
    (net (code "47") (name "/VBAT") (class "Default")
      (node (ref "BAT_CON") (pin "+") (pinfunction "+_+") (pintype "passive"))
      (node (ref "R_BAT") (pin "1") (pinfunction "1_1") (pintype "passive"))
      (node (ref "SW_ELETT") (pin "1") (pinfunction "O_1") (pintype "passive"))
      (node (ref "SW_MOT") (pin "1") (pinfunction "O_1") (pintype "passive"))
    )
    (net (code "48") (name "GND") (class "Default")
      (node (ref "BAT_CON") (pin "-") (pinfunction "-_-") (pintype "passive"))
      (node (ref "BT_CON") (pin "2") (pinfunction "2_2") (pintype "bidirectional"))
      (node (ref "C10") (pin "2") (pinfunction "2_2") (pintype "passive"))
      (node (ref "C19") (pin "2") (pinfunction "2_2") (pintype "passive"))
      (node (ref "C2") (pin "2") (pinfunction "2_2") (pintype "passive"))
      (node (ref "C20") (pin "2") (pinfunction "2_2") (pintype "passive"))
      (node (ref "C3") (pin "2") (pinfunction "2_2") (pintype "passive"))
      (node (ref "C4") (pin "2") (pinfunction "2_2") (pintype "passive"))
      (node (ref "C5") (pin "2") (pinfunction "2_2") (pintype "passive"))
      (node (ref "C6") (pin "2") (pinfunction "2_2") (pintype "passive"))
      (node (ref "C7") (pin "2") (pinfunction "-_2") (pintype "bidirectional"))
      (node (ref "C8") (pin "2") (pinfunction "2_2") (pintype "passive"))
      (node (ref "CB1") (pin "2") (pinfunction "2_2") (pintype "passive"))
      (node (ref "CB2") (pin "2") (pinfunction "2_2") (pintype "passive"))
      (node (ref "CB3") (pin "2") (pinfunction "2_2") (pintype "passive"))
      (node (ref "CB4") (pin "2") (pinfunction "2_2") (pintype "passive"))
      (node (ref "CB5") (pin "2") (pinfunction "2_2") (pintype "passive"))
      (node (ref "EXTR_3V3") (pin "2") (pinfunction "2_2") (pintype "bidirectional"))
      (node (ref "IC1") (pin "4") (pinfunction "GND_4") (pintype "power_in"))
      (node (ref "IC1") (pin "8") (pinfunction "GND_EP_8") (pintype "power_in"))
      (node (ref "LS_1") (pin "4") (pinfunction "4_4") (pintype "bidirectional"))
      (node (ref "LS_2") (pin "4") (pinfunction "4_4") (pintype "bidirectional"))
      (node (ref "LS_3") (pin "4") (pinfunction "4_4") (pintype "bidirectional"))
      (node (ref "LS_4") (pin "4") (pinfunction "4_4") (pintype "bidirectional"))
      (node (ref "L_BAT") (pin "C") (pinfunction "C_C") (pintype "passive"))
      (node (ref "L_ELETT") (pin "C") (pinfunction "C_C") (pintype "passive"))
      (node (ref "L_MOT") (pin "C") (pinfunction "C_C") (pintype "passive"))
      (node (ref "R11") (pin "2") (pinfunction "2_2") (pintype "passive"))
      (node (ref "R15") (pin "2") (pinfunction "2_2") (pintype "passive"))
      (node (ref "R19") (pin "2") (pinfunction "2_2") (pintype "passive"))
      (node (ref "R2") (pin "1") (pinfunction "1_1") (pintype "passive"))
      (node (ref "R7") (pin "2") (pinfunction "2_2") (pintype "passive"))
      (node (ref "S1") (pin "2") (pinfunction "GND_2") (pintype "power_in"))
      (node (ref "S10") (pin "2") (pinfunction "GND_2") (pintype "power_in"))
      (node (ref "S11") (pin "2") (pinfunction "GND_2") (pintype "power_in"))
      (node (ref "S12") (pin "2") (pinfunction "GND_2") (pintype "power_in"))
      (node (ref "S13") (pin "2") (pinfunction "GND_2") (pintype "power_in"))
      (node (ref "S14") (pin "2") (pinfunction "GND_2") (pintype "power_in"))
      (node (ref "S15") (pin "2") (pinfunction "GND_2") (pintype "power_in"))
      (node (ref "S16") (pin "2") (pinfunction "GND_2") (pintype "power_in"))
      (node (ref "S17") (pin "2") (pinfunction "GND_2") (pintype "power_in"))
      (node (ref "S18") (pin "2") (pinfunction "GND_2") (pintype "power_in"))
      (node (ref "S19") (pin "2") (pinfunction "GND_2") (pintype "power_in"))
      (node (ref "S2") (pin "2") (pinfunction "GND_2") (pintype "power_in"))
      (node (ref "S20") (pin "2") (pinfunction "GND_2") (pintype "power_in"))
      (node (ref "S3") (pin "2") (pinfunction "GND_2") (pintype "power_in"))
      (node (ref "S4") (pin "2") (pinfunction "GND_2") (pintype "power_in"))
      (node (ref "S5") (pin "2") (pinfunction "GND_2") (pintype "power_in"))
      (node (ref "S6") (pin "2") (pinfunction "GND_2") (pintype "power_in"))
      (node (ref "S7") (pin "2") (pinfunction "GND_2") (pintype "power_in"))
      (node (ref "S8") (pin "2") (pinfunction "GND_2") (pintype "power_in"))
      (node (ref "S9") (pin "2") (pinfunction "GND_2") (pintype "power_in"))
      (node (ref "SW_ELETT") (pin "3") (pinfunction "S_3") (pintype "passive"))
      (node (ref "SW_MOT") (pin "3") (pinfunction "S_3") (pintype "passive"))
      (node (ref "U$1") (pin "GND1") (pinfunction "GND1_GND1") (pintype "bidirectional"))
      (node (ref "U$1") (pin "GND2") (pinfunction "GND2_GND2") (pintype "bidirectional"))
      (node (ref "U$1") (pin "GND3") (pinfunction "GND3_GND3") (pintype "bidirectional"))
      (node (ref "U$1") (pin "GND4") (pinfunction "GND4_GND4") (pintype "bidirectional"))
      (node (ref "U$1") (pin "GND5") (pinfunction "GND5_GND5") (pintype "bidirectional"))
      (node (ref "U$1") (pin "GND6") (pinfunction "GND6_GND6") (pintype "bidirectional"))
      (node (ref "U$2") (pin "GND") (pinfunction "GND_GND") (pintype "bidirectional"))
      (node (ref "U$2") (pin "PAD1") (pinfunction "PAD1_PAD1") (pintype "bidirectional"))
      (node (ref "U$2") (pin "PAD2") (pinfunction "PAD2_PAD2") (pintype "bidirectional"))
      (node (ref "U$3") (pin "GND") (pinfunction "GND_GND") (pintype "bidirectional"))
    )
    (net (code "49") (name "Net-(DRV1-IN_A)") (class "Default")
      (node (ref "DRV1") (pin "3") (pinfunction "IN_A_3") (pintype "bidirectional"))
      (node (ref "R5") (pin "2") (pinfunction "2_2") (pintype "passive"))
    )
    (net (code "50") (name "Net-(DRV1-IN_B)") (class "Default")
      (node (ref "DRV1") (pin "6") (pinfunction "IN_B_6") (pintype "bidirectional"))
      (node (ref "R6") (pin "2") (pinfunction "2_2") (pintype "passive"))
    )
    (net (code "51") (name "Net-(DRV1-PWM)") (class "Default")
      (node (ref "DRV1") (pin "11") (pinfunction "PWM_11") (pintype "bidirectional"))
      (node (ref "R8") (pin "1") (pinfunction "1_1") (pintype "passive"))
    )
    (net (code "52") (name "Net-(DRV2-IN_A)") (class "Default")
      (node (ref "DRV2") (pin "3") (pinfunction "IN_A_3") (pintype "bidirectional"))
      (node (ref "R13") (pin "2") (pinfunction "2_2") (pintype "passive"))
    )
    (net (code "53") (name "Net-(DRV2-IN_B)") (class "Default")
      (node (ref "DRV2") (pin "6") (pinfunction "IN_B_6") (pintype "bidirectional"))
      (node (ref "R14") (pin "2") (pinfunction "2_2") (pintype "passive"))
    )
    (net (code "54") (name "Net-(DRV2-PWM)") (class "Default")
      (node (ref "DRV2") (pin "11") (pinfunction "PWM_11") (pintype "bidirectional"))
      (node (ref "R16") (pin "1") (pinfunction "1_1") (pintype "passive"))
    )
    (net (code "55") (name "Net-(DRV3-IN_A)") (class "Default")
      (node (ref "DRV3") (pin "3") (pinfunction "IN_A_3") (pintype "bidirectional"))
      (node (ref "R9") (pin "2") (pinfunction "2_2") (pintype "passive"))
    )
    (net (code "56") (name "Net-(DRV3-IN_B)") (class "Default")
      (node (ref "DRV3") (pin "6") (pinfunction "IN_B_6") (pintype "bidirectional"))
      (node (ref "R10") (pin "2") (pinfunction "2_2") (pintype "passive"))
    )
    (net (code "57") (name "Net-(DRV3-PWM)") (class "Default")
      (node (ref "DRV3") (pin "11") (pinfunction "PWM_11") (pintype "bidirectional"))
      (node (ref "R12") (pin "1") (pinfunction "1_1") (pintype "passive"))
    )
    (net (code "58") (name "Net-(DRV4-IN_A)") (class "Default")
      (node (ref "DRV4") (pin "3") (pinfunction "IN_A_3") (pintype "bidirectional"))
      (node (ref "R17") (pin "2") (pinfunction "2_2") (pintype "passive"))
    )
    (net (code "59") (name "Net-(DRV4-IN_B)") (class "Default")
      (node (ref "DRV4") (pin "6") (pinfunction "IN_B_6") (pintype "bidirectional"))
      (node (ref "R18") (pin "2") (pinfunction "2_2") (pintype "passive"))
    )
    (net (code "60") (name "Net-(DRV4-PWM)") (class "Default")
      (node (ref "DRV4") (pin "11") (pinfunction "PWM_11") (pintype "bidirectional"))
      (node (ref "R20") (pin "1") (pinfunction "1_1") (pintype "passive"))
    )
    (net (code "61") (name "Net-(IC1-FB)") (class "Default")
      (node (ref "C9") (pin "1") (pinfunction "1_1") (pintype "passive"))
      (node (ref "IC1") (pin "6") (pinfunction "FB_6") (pintype "bidirectional"))
      (node (ref "R2") (pin "2") (pinfunction "2_2") (pintype "passive"))
      (node (ref "R3") (pin "2") (pinfunction "2_2") (pintype "passive"))
    )
    (net (code "62") (name "Net-(IC1-RON)") (class "Default")
      (node (ref "IC1") (pin "2") (pinfunction "RON_2") (pintype "bidirectional"))
      (node (ref "R1") (pin "2") (pinfunction "2_2") (pintype "passive"))
    )
    (net (code "63") (name "Net-(IC1-SS)") (class "Default")
      (node (ref "C4") (pin "1") (pinfunction "1_1") (pintype "passive"))
      (node (ref "IC1") (pin "5") (pinfunction "SS_5") (pintype "bidirectional"))
    )
    (net (code "64") (name "Net-(IC1-VOUT)") (class "Default")
      (node (ref "IC1") (pin "7") (pinfunction "VOUT_7") (pintype "output"))
      (node (ref "R_ELETT") (pin "2") (pinfunction "2_2") (pintype "passive"))
    )
    (net (code "65") (name "Net-(L_BAT-PadA)") (class "Default")
      (node (ref "L_BAT") (pin "A") (pinfunction "A_A") (pintype "passive"))
      (node (ref "R_BAT") (pin "2") (pinfunction "2_2") (pintype "passive"))
    )
    (net (code "66") (name "Net-(L_ELETT-PadA)") (class "Default")
      (node (ref "L_ELETT") (pin "A") (pinfunction "A_A") (pintype "passive"))
      (node (ref "R_ELETT") (pin "1") (pinfunction "1_1") (pintype "passive"))
    )
    (net (code "67") (name "Net-(L_MOT-PadA)") (class "Default")
      (node (ref "L_MOT") (pin "A") (pinfunction "A_A") (pintype "passive"))
      (node (ref "R_MOT") (pin "1") (pinfunction "1_1") (pintype "passive"))
    )
    (net (code "68") (name "Net-(M1+-PadC)") (class "Default")
      (node (ref "M1+") (pin "C") (pinfunction "C_C") (pintype "passive"))
      (node (ref "M1-") (pin "C") (pinfunction "C_C") (pintype "passive"))
      (node (ref "R7") (pin "1") (pinfunction "1_1") (pintype "passive"))
    )
    (net (code "69") (name "Net-(M2+-PadC)") (class "Default")
      (node (ref "M2+") (pin "C") (pinfunction "C_C") (pintype "passive"))
      (node (ref "M2-") (pin "C") (pinfunction "C_C") (pintype "passive"))
      (node (ref "R15") (pin "1") (pinfunction "1_1") (pintype "passive"))
    )
    (net (code "70") (name "Net-(M3+-PadC)") (class "Default")
      (node (ref "M3+") (pin "C") (pinfunction "C_C") (pintype "passive"))
      (node (ref "M3-") (pin "C") (pinfunction "C_C") (pintype "passive"))
      (node (ref "R11") (pin "1") (pinfunction "1_1") (pintype "passive"))
    )
    (net (code "71") (name "Net-(M4+-PadC)") (class "Default")
      (node (ref "M4+") (pin "C") (pinfunction "C_C") (pintype "passive"))
      (node (ref "M4-") (pin "C") (pinfunction "C_C") (pintype "passive"))
      (node (ref "R19") (pin "1") (pinfunction "1_1") (pintype "passive"))
    )
    (net (code "72") (name "Net-(S1-OUT)") (class "Default")
      (node (ref "CB1") (pin "1") (pinfunction "1_1") (pintype "passive"))
      (node (ref "RB1") (pin "2") (pinfunction "2_2") (pintype "passive"))
      (node (ref "S1") (pin "1") (pinfunction "OUT_1") (pintype "output"))
      (node (ref "S2") (pin "3") (pinfunction "VCC_3") (pintype "power_in"))
      (node (ref "S3") (pin "1") (pinfunction "OUT_1") (pintype "output"))
      (node (ref "S4") (pin "3") (pinfunction "VCC_3") (pintype "power_in"))
    )
    (net (code "73") (name "Net-(S5-OUT)") (class "Default")
      (node (ref "CB2") (pin "1") (pinfunction "1_1") (pintype "passive"))
      (node (ref "RB2") (pin "2") (pinfunction "2_2") (pintype "passive"))
      (node (ref "S5") (pin "1") (pinfunction "OUT_1") (pintype "output"))
      (node (ref "S6") (pin "3") (pinfunction "VCC_3") (pintype "power_in"))
      (node (ref "S7") (pin "1") (pinfunction "OUT_1") (pintype "output"))
      (node (ref "S8") (pin "3") (pinfunction "VCC_3") (pintype "power_in"))
    )
    (net (code "74") (name "Net-(S10-VCC)") (class "Default")
      (node (ref "CB3") (pin "1") (pinfunction "1_1") (pintype "passive"))
      (node (ref "RB3") (pin "2") (pinfunction "2_2") (pintype "passive"))
      (node (ref "S10") (pin "3") (pinfunction "VCC_3") (pintype "power_in"))
      (node (ref "S11") (pin "1") (pinfunction "OUT_1") (pintype "output"))
      (node (ref "S12") (pin "3") (pinfunction "VCC_3") (pintype "power_in"))
      (node (ref "S9") (pin "1") (pinfunction "OUT_1") (pintype "output"))
    )
    (net (code "75") (name "Net-(S13-OUT)") (class "Default")
      (node (ref "CB4") (pin "1") (pinfunction "1_1") (pintype "passive"))
      (node (ref "RB4") (pin "2") (pinfunction "2_2") (pintype "passive"))
      (node (ref "S13") (pin "1") (pinfunction "OUT_1") (pintype "output"))
      (node (ref "S14") (pin "3") (pinfunction "VCC_3") (pintype "power_in"))
      (node (ref "S15") (pin "1") (pinfunction "OUT_1") (pintype "output"))
      (node (ref "S16") (pin "3") (pinfunction "VCC_3") (pintype "power_in"))
    )
    (net (code "76") (name "Net-(S17-OUT)") (class "Default")
      (node (ref "CB5") (pin "1") (pinfunction "1_1") (pintype "passive"))
      (node (ref "RB5") (pin "2") (pinfunction "2_2") (pintype "passive"))
      (node (ref "S17") (pin "1") (pinfunction "OUT_1") (pintype "output"))
      (node (ref "S18") (pin "3") (pinfunction "VCC_3") (pintype "power_in"))
      (node (ref "S19") (pin "1") (pinfunction "OUT_1") (pintype "output"))
      (node (ref "S20") (pin "3") (pinfunction "VCC_3") (pintype "power_in"))
    )
    (net (code "77") (name "V-") (class "Default")
      (node (ref "C1") (pin "2") (pinfunction "-_2") (pintype "bidirectional"))
      (node (ref "C11") (pin "-") (pinfunction "-_-") (pintype "passive"))
      (node (ref "C12") (pin "2") (pinfunction "2_2") (pintype "passive"))
      (node (ref "C13") (pin "-") (pinfunction "-_-") (pintype "passive"))
      (node (ref "C14") (pin "2") (pinfunction "2_2") (pintype "passive"))
      (node (ref "C15") (pin "-") (pinfunction "-_-") (pintype "passive"))
      (node (ref "C16") (pin "2") (pinfunction "2_2") (pintype "passive"))
      (node (ref "C17") (pin "-") (pinfunction "-_-") (pintype "passive"))
      (node (ref "C18") (pin "2") (pinfunction "2_2") (pintype "passive"))
      (node (ref "DRV1") (pin "1") (pinfunction "GND_A_1_1") (pintype "bidirectional"))
      (node (ref "DRV1") (pin "16") (pinfunction "GND_A_2_16") (pintype "bidirectional"))
      (node (ref "DRV1") (pin "8") (pinfunction "GND_B_1_8") (pintype "bidirectional"))
      (node (ref "DRV1") (pin "9") (pinfunction "GND_B_2_9") (pintype "bidirectional"))
      (node (ref "DRV2") (pin "1") (pinfunction "GND_A_1_1") (pintype "bidirectional"))
      (node (ref "DRV2") (pin "16") (pinfunction "GND_A_2_16") (pintype "bidirectional"))
      (node (ref "DRV2") (pin "8") (pinfunction "GND_B_1_8") (pintype "bidirectional"))
      (node (ref "DRV2") (pin "9") (pinfunction "GND_B_2_9") (pintype "bidirectional"))
      (node (ref "DRV3") (pin "1") (pinfunction "GND_A_1_1") (pintype "bidirectional"))
      (node (ref "DRV3") (pin "16") (pinfunction "GND_A_2_16") (pintype "bidirectional"))
      (node (ref "DRV3") (pin "8") (pinfunction "GND_B_1_8") (pintype "bidirectional"))
      (node (ref "DRV3") (pin "9") (pinfunction "GND_B_2_9") (pintype "bidirectional"))
      (node (ref "DRV4") (pin "1") (pinfunction "GND_A_1_1") (pintype "bidirectional"))
      (node (ref "DRV4") (pin "16") (pinfunction "GND_A_2_16") (pintype "bidirectional"))
      (node (ref "DRV4") (pin "8") (pinfunction "GND_B_1_8") (pintype "bidirectional"))
      (node (ref "DRV4") (pin "9") (pinfunction "GND_B_2_9") (pintype "bidirectional"))
    )
    (net (code "78") (name "VMOT") (class "Default")
      (node (ref "C1") (pin "1") (pinfunction "+_1") (pintype "bidirectional"))
      (node (ref "R_MOT") (pin "2") (pinfunction "2_2") (pintype "passive"))
      (node (ref "SW_MOT") (pin "2") (pinfunction "P_2") (pintype "passive"))
    )
    (net (code "79") (name "unconnected-(BT_CON-Pad3)") (class "Default")
      (node (ref "BT_CON") (pin "3") (pinfunction "3_3") (pintype "bidirectional"))
    )
    (net (code "80") (name "unconnected-(BT_CON-Pad4)") (class "Default")
      (node (ref "BT_CON") (pin "4") (pinfunction "4_4") (pintype "bidirectional"))
    )
    (net (code "81") (name "unconnected-(DRV1-CS-Pad13)") (class "Default")
      (node (ref "DRV1") (pin "13") (pinfunction "CS_13") (pintype "bidirectional"))
    )
    (net (code "82") (name "unconnected-(DRV1-SEL_0-Pad14)") (class "Default")
      (node (ref "DRV1") (pin "14") (pinfunction "SEL_0_14") (pintype "bidirectional"))
    )
    (net (code "83") (name "unconnected-(DRV2-CS-Pad13)") (class "Default")
      (node (ref "DRV2") (pin "13") (pinfunction "CS_13") (pintype "bidirectional"))
    )
    (net (code "84") (name "unconnected-(DRV2-SEL_0-Pad14)") (class "Default")
      (node (ref "DRV2") (pin "14") (pinfunction "SEL_0_14") (pintype "bidirectional"))
    )
    (net (code "85") (name "unconnected-(DRV3-CS-Pad13)") (class "Default")
      (node (ref "DRV3") (pin "13") (pinfunction "CS_13") (pintype "bidirectional"))
    )
    (net (code "86") (name "unconnected-(DRV3-SEL_0-Pad14)") (class "Default")
      (node (ref "DRV3") (pin "14") (pinfunction "SEL_0_14") (pintype "bidirectional"))
    )
    (net (code "87") (name "unconnected-(DRV4-CS-Pad13)") (class "Default")
      (node (ref "DRV4") (pin "13") (pinfunction "CS_13") (pintype "bidirectional"))
    )
    (net (code "88") (name "unconnected-(DRV4-SEL_0-Pad14)") (class "Default")
      (node (ref "DRV4") (pin "14") (pinfunction "SEL_0_14") (pintype "bidirectional"))
    )
    (net (code "89") (name "unconnected-(IC1-EN-Pad3)") (class "Default")
      (node (ref "IC1") (pin "3") (pinfunction "EN_3") (pintype "bidirectional"))
    )
    (net (code "90") (name "unconnected-(LS_1-Pad2)") (class "Default")
      (node (ref "LS_1") (pin "2") (pinfunction "2_2") (pintype "bidirectional"))
    )
    (net (code "91") (name "unconnected-(LS_1-Pad3)") (class "Default")
      (node (ref "LS_1") (pin "3") (pinfunction "3_3") (pintype "bidirectional"))
    )
    (net (code "92") (name "unconnected-(LS_2-Pad2)") (class "Default")
      (node (ref "LS_2") (pin "2") (pinfunction "2_2") (pintype "bidirectional"))
    )
    (net (code "93") (name "unconnected-(LS_2-Pad3)") (class "Default")
      (node (ref "LS_2") (pin "3") (pinfunction "3_3") (pintype "bidirectional"))
    )
    (net (code "94") (name "unconnected-(LS_3-Pad2)") (class "Default")
      (node (ref "LS_3") (pin "2") (pinfunction "2_2") (pintype "bidirectional"))
    )
    (net (code "95") (name "unconnected-(LS_3-Pad3)") (class "Default")
      (node (ref "LS_3") (pin "3") (pinfunction "3_3") (pintype "bidirectional"))
    )
    (net (code "96") (name "unconnected-(LS_4-Pad2)") (class "Default")
      (node (ref "LS_4") (pin "2") (pinfunction "2_2") (pintype "bidirectional"))
    )
    (net (code "97") (name "unconnected-(LS_4-Pad3)") (class "Default")
      (node (ref "LS_4") (pin "3") (pinfunction "3_3") (pintype "bidirectional"))
    )
    (net (code "98") (name "unconnected-(SV1-Pad1)") (class "Default")
      (node (ref "SV1") (pin "1") (pinfunction "1_1") (pintype "passive"))
    )
    (net (code "99") (name "unconnected-(SV1-Pad2)") (class "Default")
      (node (ref "SV1") (pin "2") (pinfunction "2_2") (pintype "passive"))
    )
    (net (code "100") (name "unconnected-(SV1-Pad3)") (class "Default")
      (node (ref "SV1") (pin "3") (pinfunction "3_3") (pintype "passive"))
    )
    (net (code "101") (name "unconnected-(SV1-Pad4)") (class "Default")
      (node (ref "SV1") (pin "4") (pinfunction "4_4") (pintype "passive"))
    )
    (net (code "102") (name "unconnected-(SV1-Pad5)") (class "Default")
      (node (ref "SV1") (pin "5") (pinfunction "5_5") (pintype "passive"))
    )
    (net (code "103") (name "unconnected-(SV1-Pad6)") (class "Default")
      (node (ref "SV1") (pin "6") (pinfunction "6_6") (pintype "passive"))
    )
    (net (code "104") (name "unconnected-(SV1-Pad7)") (class "Default")
      (node (ref "SV1") (pin "7") (pinfunction "7_7") (pintype "passive"))
    )
    (net (code "105") (name "unconnected-(SV1-Pad8)") (class "Default")
      (node (ref "SV1") (pin "8") (pinfunction "8_8") (pintype "passive"))
    )
    (net (code "106") (name "unconnected-(SV1-Pad9)") (class "Default")
      (node (ref "SV1") (pin "9") (pinfunction "9_9") (pintype "passive"))
    )
    (net (code "107") (name "unconnected-(SV1-Pad10)") (class "Default")
      (node (ref "SV1") (pin "10") (pinfunction "10_10") (pintype "passive"))
    )
    (net (code "108") (name "unconnected-(SV1-Pad11)") (class "Default")
      (node (ref "SV1") (pin "11") (pinfunction "11_11") (pintype "passive"))
    )
    (net (code "109") (name "unconnected-(SV1-Pad12)") (class "Default")
      (node (ref "SV1") (pin "12") (pinfunction "12_12") (pintype "passive"))
    )
    (net (code "110") (name "unconnected-(SV2-Pad1)") (class "Default")
      (node (ref "SV2") (pin "1") (pinfunction "1_1") (pintype "passive"))
    )
    (net (code "111") (name "unconnected-(SV2-Pad2)") (class "Default")
      (node (ref "SV2") (pin "2") (pinfunction "2_2") (pintype "passive"))
    )
    (net (code "112") (name "unconnected-(SV2-Pad5)") (class "Default")
      (node (ref "SV2") (pin "5") (pinfunction "5_5") (pintype "passive"))
    )
    (net (code "113") (name "unconnected-(SV2-Pad6)") (class "Default")
      (node (ref "SV2") (pin "6") (pinfunction "6_6") (pintype "passive"))
    )
    (net (code "114") (name "unconnected-(SV2-Pad7)") (class "Default")
      (node (ref "SV2") (pin "7") (pinfunction "7_7") (pintype "passive"))
    )
    (net (code "115") (name "unconnected-(SV2-Pad8)") (class "Default")
      (node (ref "SV2") (pin "8") (pinfunction "8_8") (pintype "passive"))
    )
    (net (code "116") (name "unconnected-(SV2-Pad9)") (class "Default")
      (node (ref "SV2") (pin "9") (pinfunction "9_9") (pintype "passive"))
    )
    (net (code "117") (name "unconnected-(SV2-Pad10)") (class "Default")
      (node (ref "SV2") (pin "10") (pinfunction "10_10") (pintype "passive"))
    )
    (net (code "118") (name "unconnected-(SV2-Pad11)") (class "Default")
      (node (ref "SV2") (pin "11") (pinfunction "11_11") (pintype "passive"))
    )
    (net (code "119") (name "unconnected-(SV2-Pad12)") (class "Default")
      (node (ref "SV2") (pin "12") (pinfunction "12_12") (pintype "passive"))
    )
    (net (code "120") (name "unconnected-(SV3-Pad1)") (class "Default")
      (node (ref "SV3") (pin "1") (pinfunction "1_1") (pintype "passive"))
    )
    (net (code "121") (name "unconnected-(SV3-Pad2)") (class "Default")
      (node (ref "SV3") (pin "2") (pinfunction "2_2") (pintype "passive"))
    )
    (net (code "122") (name "unconnected-(SV3-Pad3)") (class "Default")
      (node (ref "SV3") (pin "3") (pinfunction "3_3") (pintype "passive"))
    )
    (net (code "123") (name "unconnected-(SV3-Pad4)") (class "Default")
      (node (ref "SV3") (pin "4") (pinfunction "4_4") (pintype "passive"))
    )
    (net (code "124") (name "unconnected-(SV3-Pad5)") (class "Default")
      (node (ref "SV3") (pin "5") (pinfunction "5_5") (pintype "passive"))
    )
    (net (code "125") (name "unconnected-(SV3-Pad6)") (class "Default")
      (node (ref "SV3") (pin "6") (pinfunction "6_6") (pintype "passive"))
    )
    (net (code "126") (name "unconnected-(SV3-Pad7)") (class "Default")
      (node (ref "SV3") (pin "7") (pinfunction "7_7") (pintype "passive"))
    )
    (net (code "127") (name "unconnected-(SV3-Pad8)") (class "Default")
      (node (ref "SV3") (pin "8") (pinfunction "8_8") (pintype "passive"))
    )
    (net (code "128") (name "unconnected-(SV3-Pad9)") (class "Default")
      (node (ref "SV3") (pin "9") (pinfunction "9_9") (pintype "passive"))
    )
    (net (code "129") (name "unconnected-(SV3-Pad10)") (class "Default")
      (node (ref "SV3") (pin "10") (pinfunction "10_10") (pintype "passive"))
    )
    (net (code "130") (name "unconnected-(SV3-Pad11)") (class "Default")
      (node (ref "SV3") (pin "11") (pinfunction "11_11") (pintype "passive"))
    )
    (net (code "131") (name "unconnected-(SV3-Pad12)") (class "Default")
      (node (ref "SV3") (pin "12") (pinfunction "12_12") (pintype "passive"))
    )
    (net (code "132") (name "unconnected-(SV4-Pad1)") (class "Default")
      (node (ref "SV4") (pin "1") (pinfunction "1_1") (pintype "passive"))
    )
    (net (code "133") (name "unconnected-(SV4-Pad2)") (class "Default")
      (node (ref "SV4") (pin "2") (pinfunction "2_2") (pintype "passive"))
    )
    (net (code "134") (name "unconnected-(SV4-Pad3)") (class "Default")
      (node (ref "SV4") (pin "3") (pinfunction "3_3") (pintype "passive"))
    )
    (net (code "135") (name "unconnected-(SV4-Pad4)") (class "Default")
      (node (ref "SV4") (pin "4") (pinfunction "4_4") (pintype "passive"))
    )
    (net (code "136") (name "unconnected-(SV4-Pad5)") (class "Default")
      (node (ref "SV4") (pin "5") (pinfunction "5_5") (pintype "passive"))
    )
    (net (code "137") (name "unconnected-(SV4-Pad6)") (class "Default")
      (node (ref "SV4") (pin "6") (pinfunction "6_6") (pintype "passive"))
    )
    (net (code "138") (name "unconnected-(SV4-Pad7)") (class "Default")
      (node (ref "SV4") (pin "7") (pinfunction "7_7") (pintype "passive"))
    )
    (net (code "139") (name "unconnected-(SV4-Pad8)") (class "Default")
      (node (ref "SV4") (pin "8") (pinfunction "8_8") (pintype "passive"))
    )
    (net (code "140") (name "unconnected-(SV4-Pad9)") (class "Default")
      (node (ref "SV4") (pin "9") (pinfunction "9_9") (pintype "passive"))
    )
    (net (code "141") (name "unconnected-(SV4-Pad10)") (class "Default")
      (node (ref "SV4") (pin "10") (pinfunction "10_10") (pintype "passive"))
    )
    (net (code "142") (name "unconnected-(SV4-Pad11)") (class "Default")
      (node (ref "SV4") (pin "11") (pinfunction "11_11") (pintype "passive"))
    )
    (net (code "143") (name "unconnected-(SV4-Pad12)") (class "Default")
      (node (ref "SV4") (pin "12") (pinfunction "12_12") (pintype "passive"))
    )
    (net (code "144") (name "unconnected-(SV5-Pad1)") (class "Default")
      (node (ref "SV5") (pin "1") (pinfunction "1_1") (pintype "passive"))
    )
    (net (code "145") (name "unconnected-(SV5-Pad2)") (class "Default")
      (node (ref "SV5") (pin "2") (pinfunction "2_2") (pintype "passive"))
    )
    (net (code "146") (name "unconnected-(SV5-Pad3)") (class "Default")
      (node (ref "SV5") (pin "3") (pinfunction "3_3") (pintype "passive"))
    )
    (net (code "147") (name "unconnected-(SV5-Pad4)") (class "Default")
      (node (ref "SV5") (pin "4") (pinfunction "4_4") (pintype "passive"))
    )
    (net (code "148") (name "unconnected-(SV5-Pad5)") (class "Default")
      (node (ref "SV5") (pin "5") (pinfunction "5_5") (pintype "passive"))
    )
    (net (code "149") (name "unconnected-(SV5-Pad6)") (class "Default")
      (node (ref "SV5") (pin "6") (pinfunction "6_6") (pintype "passive"))
    )
    (net (code "150") (name "unconnected-(SV5-Pad7)") (class "Default")
      (node (ref "SV5") (pin "7") (pinfunction "7_7") (pintype "passive"))
    )
    (net (code "151") (name "unconnected-(SV5-Pad8)") (class "Default")
      (node (ref "SV5") (pin "8") (pinfunction "8_8") (pintype "passive"))
    )
    (net (code "152") (name "unconnected-(SV5-Pad9)") (class "Default")
      (node (ref "SV5") (pin "9") (pinfunction "9_9") (pintype "passive"))
    )
    (net (code "153") (name "unconnected-(SV5-Pad10)") (class "Default")
      (node (ref "SV5") (pin "10") (pinfunction "10_10") (pintype "passive"))
    )
    (net (code "154") (name "unconnected-(SV5-Pad11)") (class "Default")
      (node (ref "SV5") (pin "11") (pinfunction "11_11") (pintype "passive"))
    )
    (net (code "155") (name "unconnected-(SV5-Pad12)") (class "Default")
      (node (ref "SV5") (pin "12") (pinfunction "12_12") (pintype "passive"))
    )
    (net (code "156") (name "unconnected-(SV6-Pad1)") (class "Default")
      (node (ref "SV6") (pin "1") (pinfunction "1_1") (pintype "passive"))
    )
    (net (code "157") (name "unconnected-(SV6-Pad2)") (class "Default")
      (node (ref "SV6") (pin "2") (pinfunction "2_2") (pintype "passive"))
    )
    (net (code "158") (name "unconnected-(SV6-Pad3)") (class "Default")
      (node (ref "SV6") (pin "3") (pinfunction "3_3") (pintype "passive"))
    )
    (net (code "159") (name "unconnected-(SV6-Pad4)") (class "Default")
      (node (ref "SV6") (pin "4") (pinfunction "4_4") (pintype "passive"))
    )
    (net (code "160") (name "unconnected-(SV6-Pad5)") (class "Default")
      (node (ref "SV6") (pin "5") (pinfunction "5_5") (pintype "passive"))
    )
    (net (code "161") (name "unconnected-(SV6-Pad6)") (class "Default")
      (node (ref "SV6") (pin "6") (pinfunction "6_6") (pintype "passive"))
    )
    (net (code "162") (name "unconnected-(SV6-Pad7)") (class "Default")
      (node (ref "SV6") (pin "7") (pinfunction "7_7") (pintype "passive"))
    )
    (net (code "163") (name "unconnected-(SV6-Pad10)") (class "Default")
      (node (ref "SV6") (pin "10") (pinfunction "10_10") (pintype "passive"))
    )
    (net (code "164") (name "unconnected-(SV6-Pad11)") (class "Default")
      (node (ref "SV6") (pin "11") (pinfunction "11_11") (pintype "passive"))
    )
    (net (code "165") (name "unconnected-(SV6-Pad12)") (class "Default")
      (node (ref "SV6") (pin "12") (pinfunction "12_12") (pintype "passive"))
    )
    (net (code "166") (name "unconnected-(SV6-Pad13)") (class "Default")
      (node (ref "SV6") (pin "13") (pinfunction "13_13") (pintype "passive"))
    )
    (net (code "167") (name "unconnected-(SV6-Pad14)") (class "Default")
      (node (ref "SV6") (pin "14") (pinfunction "14_14") (pintype "passive"))
    )
    (net (code "168") (name "unconnected-(SV7-Pad1)") (class "Default")
      (node (ref "SV7") (pin "1") (pinfunction "1_1") (pintype "passive"))
    )
    (net (code "169") (name "unconnected-(SV7-Pad2)") (class "Default")
      (node (ref "SV7") (pin "2") (pinfunction "2_2") (pintype "passive"))
    )
    (net (code "170") (name "unconnected-(SV7-Pad3)") (class "Default")
      (node (ref "SV7") (pin "3") (pinfunction "3_3") (pintype "passive"))
    )
    (net (code "171") (name "unconnected-(SV8-Pad1)") (class "Default")
      (node (ref "SV8") (pin "1") (pinfunction "1_1") (pintype "passive"))
    )
    (net (code "172") (name "unconnected-(SV8-Pad2)") (class "Default")
      (node (ref "SV8") (pin "2") (pinfunction "2_2") (pintype "passive"))
    )
    (net (code "173") (name "unconnected-(SV8-Pad3)") (class "Default")
      (node (ref "SV8") (pin "3") (pinfunction "3_3") (pintype "passive"))
    )
    (net (code "174") (name "unconnected-(SV9-Pad1)") (class "Default")
      (node (ref "SV9") (pin "1") (pinfunction "1_1") (pintype "passive"))
    )
    (net (code "175") (name "unconnected-(SV9-Pad2)") (class "Default")
      (node (ref "SV9") (pin "2") (pinfunction "2_2") (pintype "passive"))
    )
    (net (code "176") (name "unconnected-(SV9-Pad3)") (class "Default")
      (node (ref "SV9") (pin "3") (pinfunction "3_3") (pintype "passive"))
    )
    (net (code "177") (name "unconnected-(SV10-Pad1)") (class "Default")
      (node (ref "SV10") (pin "1") (pinfunction "1_1") (pintype "passive"))
    )
    (net (code "178") (name "unconnected-(SV10-Pad2)") (class "Default")
      (node (ref "SV10") (pin "2") (pinfunction "2_2") (pintype "passive"))
    )
    (net (code "179") (name "unconnected-(SV10-Pad3)") (class "Default")
      (node (ref "SV10") (pin "3") (pinfunction "3_3") (pintype "passive"))
    )
    (net (code "180") (name "unconnected-(SV11-Pad1)") (class "Default")
      (node (ref "SV11") (pin "1") (pinfunction "1_1") (pintype "passive"))
    )
    (net (code "181") (name "unconnected-(SV11-Pad2)") (class "Default")
      (node (ref "SV11") (pin "2") (pinfunction "2_2") (pintype "passive"))
    )
    (net (code "182") (name "unconnected-(SV11-Pad3)") (class "Default")
      (node (ref "SV11") (pin "3") (pinfunction "3_3") (pintype "passive"))
    )
    (net (code "183") (name "unconnected-(SV12-Pad1)") (class "Default")
      (node (ref "SV12") (pin "1") (pinfunction "1_1") (pintype "passive"))
    )
    (net (code "184") (name "unconnected-(SV12-Pad2)") (class "Default")
      (node (ref "SV12") (pin "2") (pinfunction "2_2") (pintype "passive"))
    )
    (net (code "185") (name "unconnected-(SV12-Pad3)") (class "Default")
      (node (ref "SV12") (pin "3") (pinfunction "3_3") (pintype "passive"))
    )
    (net (code "186") (name "unconnected-(SV13-Pad1)") (class "Default")
      (node (ref "SV13") (pin "1") (pinfunction "1_1") (pintype "passive"))
    )
    (net (code "187") (name "unconnected-(SV13-Pad2)") (class "Default")
      (node (ref "SV13") (pin "2") (pinfunction "2_2") (pintype "passive"))
    )
    (net (code "188") (name "unconnected-(SV13-Pad3)") (class "Default")
      (node (ref "SV13") (pin "3") (pinfunction "3_3") (pintype "passive"))
    )
    (net (code "189") (name "unconnected-(SV14-Pad1)") (class "Default")
      (node (ref "SV14") (pin "1") (pinfunction "1_1") (pintype "passive"))
    )
    (net (code "190") (name "unconnected-(SV14-Pad2)") (class "Default")
      (node (ref "SV14") (pin "2") (pinfunction "2_2") (pintype "passive"))
    )
    (net (code "191") (name "unconnected-(SV14-Pad3)") (class "Default")
      (node (ref "SV14") (pin "3") (pinfunction "3_3") (pintype "passive"))
    )
    (net (code "192") (name "unconnected-(SV15-Pad1)") (class "Default")
      (node (ref "SV15") (pin "1") (pinfunction "1_1") (pintype "passive"))
    )
    (net (code "193") (name "unconnected-(SV15-Pad2)") (class "Default")
      (node (ref "SV15") (pin "2") (pinfunction "2_2") (pintype "passive"))
    )
    (net (code "194") (name "unconnected-(SV15-Pad3)") (class "Default")
      (node (ref "SV15") (pin "3") (pinfunction "3_3") (pintype "passive"))
    )
    (net (code "195") (name "unconnected-(SV16-Pad1)") (class "Default")
      (node (ref "SV16") (pin "1") (pinfunction "1_1") (pintype "passive"))
    )
    (net (code "196") (name "unconnected-(SV16-Pad2)") (class "Default")
      (node (ref "SV16") (pin "2") (pinfunction "2_2") (pintype "passive"))
    )
    (net (code "197") (name "unconnected-(SV16-Pad3)") (class "Default")
      (node (ref "SV16") (pin "3") (pinfunction "3_3") (pintype "passive"))
    )
    (net (code "198") (name "unconnected-(SV17-Pad1)") (class "Default")
      (node (ref "SV17") (pin "1") (pinfunction "1_1") (pintype "passive"))
    )
    (net (code "199") (name "unconnected-(SV17-Pad2)") (class "Default")
      (node (ref "SV17") (pin "2") (pinfunction "2_2") (pintype "passive"))
    )
    (net (code "200") (name "unconnected-(SV17-Pad3)") (class "Default")
      (node (ref "SV17") (pin "3") (pinfunction "3_3") (pintype "passive"))
    )
    (net (code "201") (name "unconnected-(SV18-Pad1)") (class "Default")
      (node (ref "SV18") (pin "1") (pinfunction "1_1") (pintype "passive"))
    )
    (net (code "202") (name "unconnected-(SV18-Pad2)") (class "Default")
      (node (ref "SV18") (pin "2") (pinfunction "2_2") (pintype "passive"))
    )
    (net (code "203") (name "unconnected-(SV18-Pad3)") (class "Default")
      (node (ref "SV18") (pin "3") (pinfunction "3_3") (pintype "passive"))
    )
    (net (code "204") (name "unconnected-(SV19-Pad1)") (class "Default")
      (node (ref "SV19") (pin "1") (pinfunction "1_1") (pintype "passive"))
    )
    (net (code "205") (name "unconnected-(SV19-Pad2)") (class "Default")
      (node (ref "SV19") (pin "2") (pinfunction "2_2") (pintype "passive"))
    )
    (net (code "206") (name "unconnected-(SV19-Pad3)") (class "Default")
      (node (ref "SV19") (pin "3") (pinfunction "3_3") (pintype "passive"))
    )
    (net (code "207") (name "unconnected-(SV20-Pad1)") (class "Default")
      (node (ref "SV20") (pin "1") (pinfunction "1_1") (pintype "passive"))
    )
    (net (code "208") (name "unconnected-(SV20-Pad2)") (class "Default")
      (node (ref "SV20") (pin "2") (pinfunction "2_2") (pintype "passive"))
    )
    (net (code "209") (name "unconnected-(SV20-Pad3)") (class "Default")
      (node (ref "SV20") (pin "3") (pinfunction "3_3") (pintype "passive"))
    )
    (net (code "210") (name "unconnected-(SV21-Pad1)") (class "Default")
      (node (ref "SV21") (pin "1") (pinfunction "1_1") (pintype "passive"))
    )
    (net (code "211") (name "unconnected-(SV21-Pad2)") (class "Default")
      (node (ref "SV21") (pin "2") (pinfunction "2_2") (pintype "passive"))
    )
    (net (code "212") (name "unconnected-(SV21-Pad3)") (class "Default")
      (node (ref "SV21") (pin "3") (pinfunction "3_3") (pintype "passive"))
    )
    (net (code "213") (name "unconnected-(SV22-Pad1)") (class "Default")
      (node (ref "SV22") (pin "1") (pinfunction "1_1") (pintype "passive"))
    )
    (net (code "214") (name "unconnected-(SV22-Pad2)") (class "Default")
      (node (ref "SV22") (pin "2") (pinfunction "2_2") (pintype "passive"))
    )
    (net (code "215") (name "unconnected-(SV22-Pad3)") (class "Default")
      (node (ref "SV22") (pin "3") (pinfunction "3_3") (pintype "passive"))
    )
    (net (code "216") (name "unconnected-(SV23-Pad1)") (class "Default")
      (node (ref "SV23") (pin "1") (pinfunction "1_1") (pintype "passive"))
    )
    (net (code "217") (name "unconnected-(SV23-Pad2)") (class "Default")
      (node (ref "SV23") (pin "2") (pinfunction "2_2") (pintype "passive"))
    )
    (net (code "218") (name "unconnected-(SV23-Pad3)") (class "Default")
      (node (ref "SV23") (pin "3") (pinfunction "3_3") (pintype "passive"))
    )
    (net (code "219") (name "unconnected-(SV24-Pad1)") (class "Default")
      (node (ref "SV24") (pin "1") (pinfunction "1_1") (pintype "passive"))
    )
    (net (code "220") (name "unconnected-(SV24-Pad2)") (class "Default")
      (node (ref "SV24") (pin "2") (pinfunction "2_2") (pintype "passive"))
    )
    (net (code "221") (name "unconnected-(SV24-Pad3)") (class "Default")
      (node (ref "SV24") (pin "3") (pinfunction "3_3") (pintype "passive"))
    )
    (net (code "222") (name "unconnected-(SV25-Pad1)") (class "Default")
      (node (ref "SV25") (pin "1") (pinfunction "1_1") (pintype "passive"))
    )
    (net (code "223") (name "unconnected-(SV25-Pad2)") (class "Default")
      (node (ref "SV25") (pin "2") (pinfunction "2_2") (pintype "passive"))
    )
    (net (code "224") (name "unconnected-(SV25-Pad3)") (class "Default")
      (node (ref "SV25") (pin "3") (pinfunction "3_3") (pintype "passive"))
    )
    (net (code "225") (name "unconnected-(SV26-Pad1)") (class "Default")
      (node (ref "SV26") (pin "1") (pinfunction "1_1") (pintype "passive"))
    )
    (net (code "226") (name "unconnected-(SV26-Pad2)") (class "Default")
      (node (ref "SV26") (pin "2") (pinfunction "2_2") (pintype "passive"))
    )
    (net (code "227") (name "unconnected-(SV26-Pad3)") (class "Default")
      (node (ref "SV26") (pin "3") (pinfunction "3_3") (pintype "passive"))
    )
    (net (code "228") (name "unconnected-(U$1-5V-Pad+5V)") (class "Default")
      (node (ref "U$1") (pin "+5V") (pinfunction "5V_+5V") (pintype "bidirectional"))
    )
    (net (code "229") (name "unconnected-(U$1-8-TX2{slash}IN1-Pad8-TX2{slash}IN2)") (class "Default")
      (node (ref "U$1") (pin "8-TX2/IN2") (pinfunction "8-TX2/IN1_8-TX2/IN2") (pintype "bidirectional"))
    )
    (net (code "230") (name "unconnected-(U$1-35{slash}TX8-Pad35-TX8)") (class "Default")
      (node (ref "U$1") (pin "35-TX8") (pinfunction "35/TX8_35-TX8") (pintype "bidirectional"))
    )
    (net (code "231") (name "unconnected-(U$1-Pad0-RX1{slash}CS1{slash}CRX2)") (class "Default")
      (node (ref "U$1") (pin "0-RX1/CS1/CRX2") (pinfunction "0-RX1/CS1/CRX2_0-RX1/CS1/CRX2") (pintype "bidirectional"))
    )
    (net (code "232") (name "unconnected-(U$1-Pad1-TX1{slash}MISO1{slash}CTX2)") (class "Default")
      (node (ref "U$1") (pin "1-TX1/MISO1/CTX2") (pinfunction "1-TX1/MISO1/CTX2_1-TX1/MISO1/CTX2") (pintype "bidirectional"))
    )
    (net (code "233") (name "unconnected-(U$1-Pad2-OUT2)") (class "Default")
      (node (ref "U$1") (pin "2-OUT2") (pinfunction "2-OUT2_2-OUT2") (pintype "bidirectional"))
    )
    (net (code "234") (name "unconnected-(U$1-Pad3-LRCLK2)") (class "Default")
      (node (ref "U$1") (pin "3-LRCLK2") (pinfunction "3-LRCLK2_3-LRCLK2") (pintype "bidirectional"))
    )
    (net (code "235") (name "unconnected-(U$1-Pad3V3-1)") (class "Default")
      (node (ref "U$1") (pin "3V3-1") (pinfunction "3V3-1_3V3-1") (pintype "bidirectional"))
    )
    (net (code "236") (name "unconnected-(U$1-Pad3V3-2)") (class "Default")
      (node (ref "U$1") (pin "3V3-2") (pinfunction "3V3-2_3V3-2") (pintype "bidirectional"))
    )
    (net (code "237") (name "unconnected-(U$1-Pad3V3-3)") (class "Default")
      (node (ref "U$1") (pin "3V3-3") (pinfunction "3V3-3_3V3-3") (pintype "bidirectional"))
    )
    (net (code "238") (name "unconnected-(U$1-Pad4-BCLK2)") (class "Default")
      (node (ref "U$1") (pin "4-BCLK2") (pinfunction "4-BCLK2_4-BCLK2") (pintype "bidirectional"))
    )
    (net (code "239") (name "unconnected-(U$1-Pad5-IN2)") (class "Default")
      (node (ref "U$1") (pin "5-IN2") (pinfunction "5-IN2_5-IN2") (pintype "bidirectional"))
    )
    (net (code "240") (name "unconnected-(U$1-Pad6-OUT1D)") (class "Default")
      (node (ref "U$1") (pin "6-OUT1D") (pinfunction "6-OUT1D_6-OUT1D") (pintype "bidirectional"))
    )
    (net (code "241") (name "unconnected-(U$1-Pad7-RX2{slash}OUT1A)") (class "Default")
      (node (ref "U$1") (pin "7-RX2/OUT1A") (pinfunction "7-RX2/OUT1A_7-RX2/OUT1A") (pintype "bidirectional"))
    )
    (net (code "242") (name "unconnected-(U$1-Pad9-OUT1C)") (class "Default")
      (node (ref "U$1") (pin "9-OUT1C") (pinfunction "9-OUT1C_9-OUT1C") (pintype "bidirectional"))
    )
    (net (code "243") (name "unconnected-(U$1-Pad12-MISO{slash}MQSL)") (class "Default")
      (node (ref "U$1") (pin "12-MISO/MQSL") (pinfunction "12-MISO/MQSL_12-MISO/MQSL") (pintype "bidirectional"))
    )
    (net (code "244") (name "unconnected-(U$1-Pad13-SCK{slash}LED)") (class "Default")
      (node (ref "U$1") (pin "13-SCK/LED") (pinfunction "13-SCK/LED_13-SCK/LED") (pintype "bidirectional"))
    )
    (net (code "245") (name "unconnected-(U$1-Pad14-A0{slash}TX3{slash}SPDIF_OUT)") (class "Default")
      (node (ref "U$1") (pin "14-A0/TX3/SPDIF_OUT") (pinfunction "14-A0/TX3/SPDIF_OUT_14-A0/TX3/SPDIF_OUT") (pintype "bidirectional"))
    )
    (net (code "246") (name "unconnected-(U$1-Pad15-A1{slash}RX3{slash}SPDIF_IN)") (class "Default")
      (node (ref "U$1") (pin "15-A1/RX3/SPDIF_IN") (pinfunction "15-A1/RX3/SPDIF_IN_15-A1/RX3/SPDIF_IN") (pintype "bidirectional"))
    )
    (net (code "247") (name "unconnected-(U$1-Pad16-A2{slash}RX4{slash}SCL1)") (class "Default")
      (node (ref "U$1") (pin "16-A2/RX4/SCL1") (pinfunction "16-A2/RX4/SCL1_16-A2/RX4/SCL1") (pintype "bidirectional"))
    )
    (net (code "248") (name "unconnected-(U$1-Pad17-A3{slash}TX4{slash}SDA1)") (class "Default")
      (node (ref "U$1") (pin "17-A3/TX4/SDA1") (pinfunction "17-A3/TX4/SDA1_17-A3/TX4/SDA1") (pintype "bidirectional"))
    )
    (net (code "249") (name "unconnected-(U$1-Pad18-A4{slash}SDA0)") (class "Default")
      (node (ref "U$1") (pin "18-A4/SDA0") (pinfunction "18-A4/SDA0_18-A4/SDA0") (pintype "bidirectional"))
    )
    (net (code "250") (name "unconnected-(U$1-Pad19-A5{slash}SCL0)") (class "Default")
      (node (ref "U$1") (pin "19-A5/SCL0") (pinfunction "19-A5/SCL0_19-A5/SCL0") (pintype "bidirectional"))
    )
    (net (code "251") (name "unconnected-(U$1-Pad20-A6{slash}TX5{slash}LRCLK1)") (class "Default")
      (node (ref "U$1") (pin "20-A6/TX5/LRCLK1") (pinfunction "20-A6/TX5/LRCLK1_20-A6/TX5/LRCLK1") (pintype "bidirectional"))
    )
    (net (code "252") (name "unconnected-(U$1-Pad21-A7{slash}RX5{slash}BCLK1)") (class "Default")
      (node (ref "U$1") (pin "21-A7/RX5/BCLK1") (pinfunction "21-A7/RX5/BCLK1_21-A7/RX5/BCLK1") (pintype "bidirectional"))
    )
    (net (code "253") (name "unconnected-(U$1-Pad22-A8{slash}CTX1)") (class "Default")
      (node (ref "U$1") (pin "22-A8/CTX1") (pinfunction "22-A8/CTX1_22-A8/CTX1") (pintype "bidirectional"))
    )
    (net (code "254") (name "unconnected-(U$1-Pad23-A9{slash}CRX1{slash}MCLK1)") (class "Default")
      (node (ref "U$1") (pin "23-A9/CRX1/MCLK1") (pinfunction "23-A9/CRX1/MCLK1_23-A9/CRX1/MCLK1") (pintype "bidirectional"))
    )
    (net (code "255") (name "unconnected-(U$1-Pad24-A10{slash}TX6{slash}SCL2)") (class "Default")
      (node (ref "U$1") (pin "24-A10/TX6/SCL2") (pinfunction "24-A10/TX6/SCL2_24-A10/TX6/SCL2") (pintype "bidirectional"))
    )
    (net (code "256") (name "unconnected-(U$1-Pad25-A11{slash}RX6{slash}SDA2)") (class "Default")
      (node (ref "U$1") (pin "25-A11/RX6/SDA2") (pinfunction "25-A11/RX6/SDA2_25-A11/RX6/SDA2") (pintype "bidirectional"))
    )
    (net (code "257") (name "unconnected-(U$1-Pad26-A12{slash}MOSI1)") (class "Default")
      (node (ref "U$1") (pin "26-A12/MOSI1") (pinfunction "26-A12/MOSI1_26-A12/MOSI1") (pintype "bidirectional"))
    )
    (net (code "258") (name "unconnected-(U$1-Pad27-A13{slash}SCK1)") (class "Default")
      (node (ref "U$1") (pin "27-A13/SCK1") (pinfunction "27-A13/SCK1_27-A13/SCK1") (pintype "bidirectional"))
    )
    (net (code "259") (name "unconnected-(U$1-Pad28-RX7)") (class "Default")
      (node (ref "U$1") (pin "28-RX7") (pinfunction "28-RX7_28-RX7") (pintype "bidirectional"))
    )
    (net (code "260") (name "unconnected-(U$1-Pad29-TX7)") (class "Default")
      (node (ref "U$1") (pin "29-TX7") (pinfunction "29-TX7_29-TX7") (pintype "bidirectional"))
    )
    (net (code "261") (name "unconnected-(U$1-Pad30-CRX3)") (class "Default")
      (node (ref "U$1") (pin "30-CRX3") (pinfunction "30-CRX3_30-CRX3") (pintype "bidirectional"))
    )
    (net (code "262") (name "unconnected-(U$1-Pad31-CTX3)") (class "Default")
      (node (ref "U$1") (pin "31-CTX3") (pinfunction "31-CTX3_31-CTX3") (pintype "bidirectional"))
    )
    (net (code "263") (name "unconnected-(U$1-Pad32-OUT1B)") (class "Default")
      (node (ref "U$1") (pin "32-OUT1B") (pinfunction "32-OUT1B_32-OUT1B") (pintype "bidirectional"))
    )
    (net (code "264") (name "unconnected-(U$1-Pad33-MCLK2)") (class "Default")
      (node (ref "U$1") (pin "33-MCLK2") (pinfunction "33-MCLK2_33-MCLK2") (pintype "bidirectional"))
    )
    (net (code "265") (name "unconnected-(U$1-Pad34-RX8)") (class "Default")
      (node (ref "U$1") (pin "34-RX8") (pinfunction "34-RX8_34-RX8") (pintype "bidirectional"))
    )
    (net (code "266") (name "unconnected-(U$1-Pad36-PWM)") (class "Default")
      (node (ref "U$1") (pin "36-PWM") (pinfunction "36-PWM_36-PWM") (pintype "bidirectional"))
    )
    (net (code "267") (name "unconnected-(U$1-Pad37-PWM)") (class "Default")
      (node (ref "U$1") (pin "37-PWM") (pinfunction "37-PWM_37-PWM") (pintype "bidirectional"))
    )
    (net (code "268") (name "unconnected-(U$1-Pad38-A14{slash}CS{slash}IN1)") (class "Default")
      (node (ref "U$1") (pin "38-A14/CS/IN1") (pinfunction "38-A14/CS/IN1_38-A14/CS/IN1") (pintype "bidirectional"))
    )
    (net (code "269") (name "unconnected-(U$1-Pad39-A15{slash}CS{slash}OUT1A)") (class "Default")
      (node (ref "U$1") (pin "39-A15/CS/OUT1A") (pinfunction "39-A15/CS/OUT1A_39-A15/CS/OUT1A") (pintype "bidirectional"))
    )
    (net (code "270") (name "unconnected-(U$1-Pad40-A16{slash}CS1)") (class "Default")
      (node (ref "U$1") (pin "40-A16/CS1") (pinfunction "40-A16/CS1_40-A16/CS1") (pintype "bidirectional"))
    )
    (net (code "271") (name "unconnected-(U$1-Pad41-A17{slash}MISO1)") (class "Default")
      (node (ref "U$1") (pin "41-A17/MISO1") (pinfunction "41-A17/MISO1_41-A17/MISO1") (pintype "bidirectional"))
    )
    (net (code "272") (name "unconnected-(U$1-PadD+)") (class "Default")
      (node (ref "U$1") (pin "D+") (pinfunction "D+_D+") (pintype "bidirectional"))
    )
    (net (code "273") (name "unconnected-(U$1-PadD-)") (class "Default")
      (node (ref "U$1") (pin "D-") (pinfunction "D-_D-") (pintype "bidirectional"))
    )
    (net (code "274") (name "unconnected-(U$1-PadDM)") (class "Default")
      (node (ref "U$1") (pin "DM") (pinfunction "DM_DM") (pintype "bidirectional"))
    )
    (net (code "275") (name "unconnected-(U$1-PadDP)") (class "Default")
      (node (ref "U$1") (pin "DP") (pinfunction "DP_DP") (pintype "bidirectional"))
    )
    (net (code "276") (name "unconnected-(U$1-PadG)") (class "Default")
      (node (ref "U$1") (pin "G") (pinfunction "G_G") (pintype "bidirectional"))
    )
    (net (code "277") (name "unconnected-(U$1-PadLED)") (class "Default")
      (node (ref "U$1") (pin "LED") (pinfunction "LED_LED") (pintype "bidirectional"))
    )
    (net (code "278") (name "unconnected-(U$1-PadON{slash}OFF)") (class "Default")
      (node (ref "U$1") (pin "ON/OFF") (pinfunction "ON/OFF_ON/OFF") (pintype "bidirectional"))
    )
    (net (code "279") (name "unconnected-(U$1-PadPROGRAM)") (class "Default")
      (node (ref "U$1") (pin "PROGRAM") (pinfunction "PROGRAM_PROGRAM") (pintype "bidirectional"))
    )
    (net (code "280") (name "unconnected-(U$1-PadR+)") (class "Default")
      (node (ref "U$1") (pin "R+") (pinfunction "R+_R+") (pintype "bidirectional"))
    )
    (net (code "281") (name "unconnected-(U$1-PadR-)") (class "Default")
      (node (ref "U$1") (pin "R-") (pinfunction "R-_R-") (pintype "bidirectional"))
    )
    (net (code "282") (name "unconnected-(U$1-PadT+)") (class "Default")
      (node (ref "U$1") (pin "T+") (pinfunction "T+_T+") (pintype "bidirectional"))
    )
    (net (code "283") (name "unconnected-(U$1-PadT-)") (class "Default")
      (node (ref "U$1") (pin "T-") (pinfunction "T-_T-") (pintype "bidirectional"))
    )
    (net (code "284") (name "unconnected-(U$1-PadVBAT)") (class "Default")
      (node (ref "U$1") (pin "VBAT") (pinfunction "VBAT_VBAT") (pintype "bidirectional"))
    )
    (net (code "285") (name "unconnected-(U$1-PadVIN)") (class "Default")
      (node (ref "U$1") (pin "VIN") (pinfunction "VIN_VIN") (pintype "bidirectional"))
    )
    (net (code "286") (name "unconnected-(U$1-PadVUSB)") (class "Default")
      (node (ref "U$1") (pin "VUSB") (pinfunction "VUSB_VUSB") (pintype "bidirectional"))
    )
    (net (code "287") (name "unconnected-(U$2-PadBOOT)") (class "Default")
      (node (ref "U$2") (pin "BOOT") (pinfunction "BOOT_BOOT") (pintype "bidirectional"))
    )
    (net (code "288") (name "unconnected-(U$2-PadP0)") (class "Default")
      (node (ref "U$2") (pin "P0") (pinfunction "P0_P0") (pintype "bidirectional"))
    )
    (net (code "289") (name "unconnected-(U$2-PadP1)") (class "Default")
      (node (ref "U$2") (pin "P1") (pinfunction "P1_P1") (pintype "bidirectional"))
    )
    (net (code "290") (name "unconnected-(U$2-PadP2)") (class "Default")
      (node (ref "U$2") (pin "P2") (pinfunction "P2_P2") (pintype "bidirectional"))
    )
    (net (code "291") (name "unconnected-(U$2-PadP3)") (class "Default")
      (node (ref "U$2") (pin "P3") (pinfunction "P3_P3") (pintype "bidirectional"))
    )
    (net (code "292") (name "unconnected-(U$2-PadP6)") (class "Default")
      (node (ref "U$2") (pin "P6") (pinfunction "P6_P6") (pintype "bidirectional"))
    )
    (net (code "293") (name "unconnected-(U$2-PadP7)") (class "Default")
      (node (ref "U$2") (pin "P7") (pinfunction "P7_P7") (pintype "bidirectional"))
    )
    (net (code "294") (name "unconnected-(U$2-PadP8)") (class "Default")
      (node (ref "U$2") (pin "P8") (pinfunction "P8_P8") (pintype "bidirectional"))
    )
    (net (code "295") (name "unconnected-(U$2-PadP9)") (class "Default")
      (node (ref "U$2") (pin "P9") (pinfunction "P9_P9") (pintype "bidirectional"))
    )
    (net (code "296") (name "unconnected-(U$2-PadRST)") (class "Default")
      (node (ref "U$2") (pin "RST") (pinfunction "RST_RST") (pintype "bidirectional"))
    )
    (net (code "297") (name "unconnected-(U$2-PadSYNC)") (class "Default")
      (node (ref "U$2") (pin "SYNC") (pinfunction "SYNC_SYNC") (pintype "bidirectional"))
    )
    (net (code "298") (name "unconnected-(U$2-PadVIN)") (class "Default")
      (node (ref "U$2") (pin "VIN") (pinfunction "VIN_VIN") (pintype "bidirectional"))
    )
    (net (code "299") (name "unconnected-(U$3-PadADR)") (class "Default")
      (node (ref "U$3") (pin "ADR") (pinfunction "ADR_ADR") (pintype "bidirectional"))
    )
    (net (code "300") (name "unconnected-(U$3-PadINT)") (class "Default")
      (node (ref "U$3") (pin "INT") (pinfunction "INT_INT") (pintype "bidirectional"))
    )
    (net (code "301") (name "unconnected-(U$3-PadPS0)") (class "Default")
      (node (ref "U$3") (pin "PS0") (pinfunction "PS0_PS0") (pintype "bidirectional"))
    )
    (net (code "302") (name "unconnected-(U$3-PadPS1)") (class "Default")
      (node (ref "U$3") (pin "PS1") (pinfunction "PS1_PS1") (pintype "bidirectional"))
    )
    (net (code "303") (name "unconnected-(U$3-PadRST)") (class "Default")
      (node (ref "U$3") (pin "RST") (pinfunction "RST_RST") (pintype "bidirectional"))
    )
    (net (code "304") (name "unconnected-(U$3-PadVIN)") (class "Default")
      (node (ref "U$3") (pin "VIN") (pinfunction "VIN_VIN") (pintype "bidirectional"))
    )
  )
)
